# element.net
KiCad netlist of a schematic drawn in EAGLE
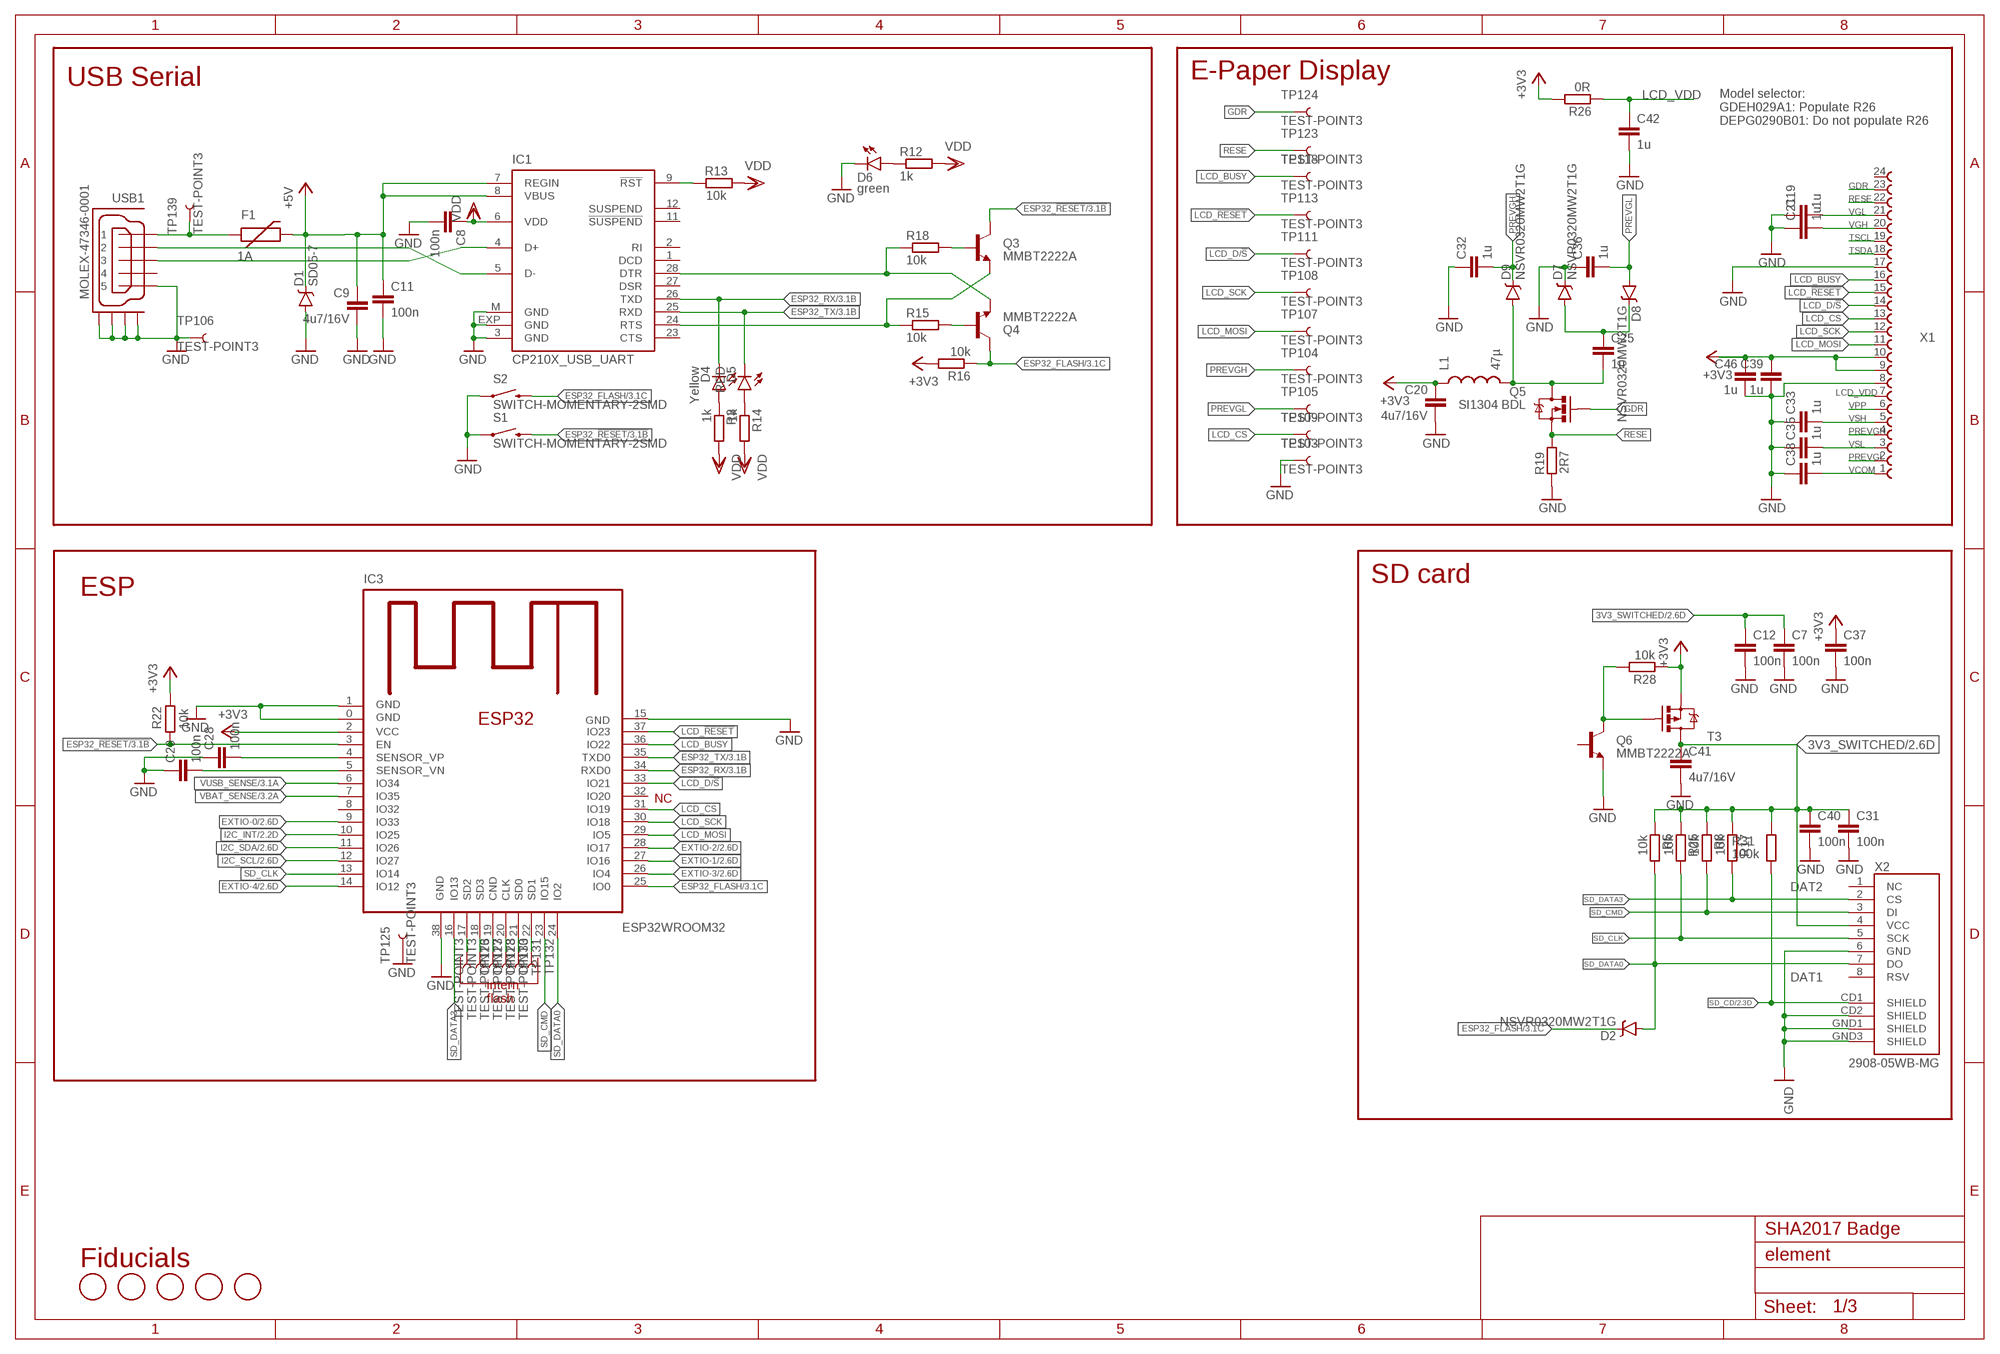
[diagram p0: schematic, sheet 1]
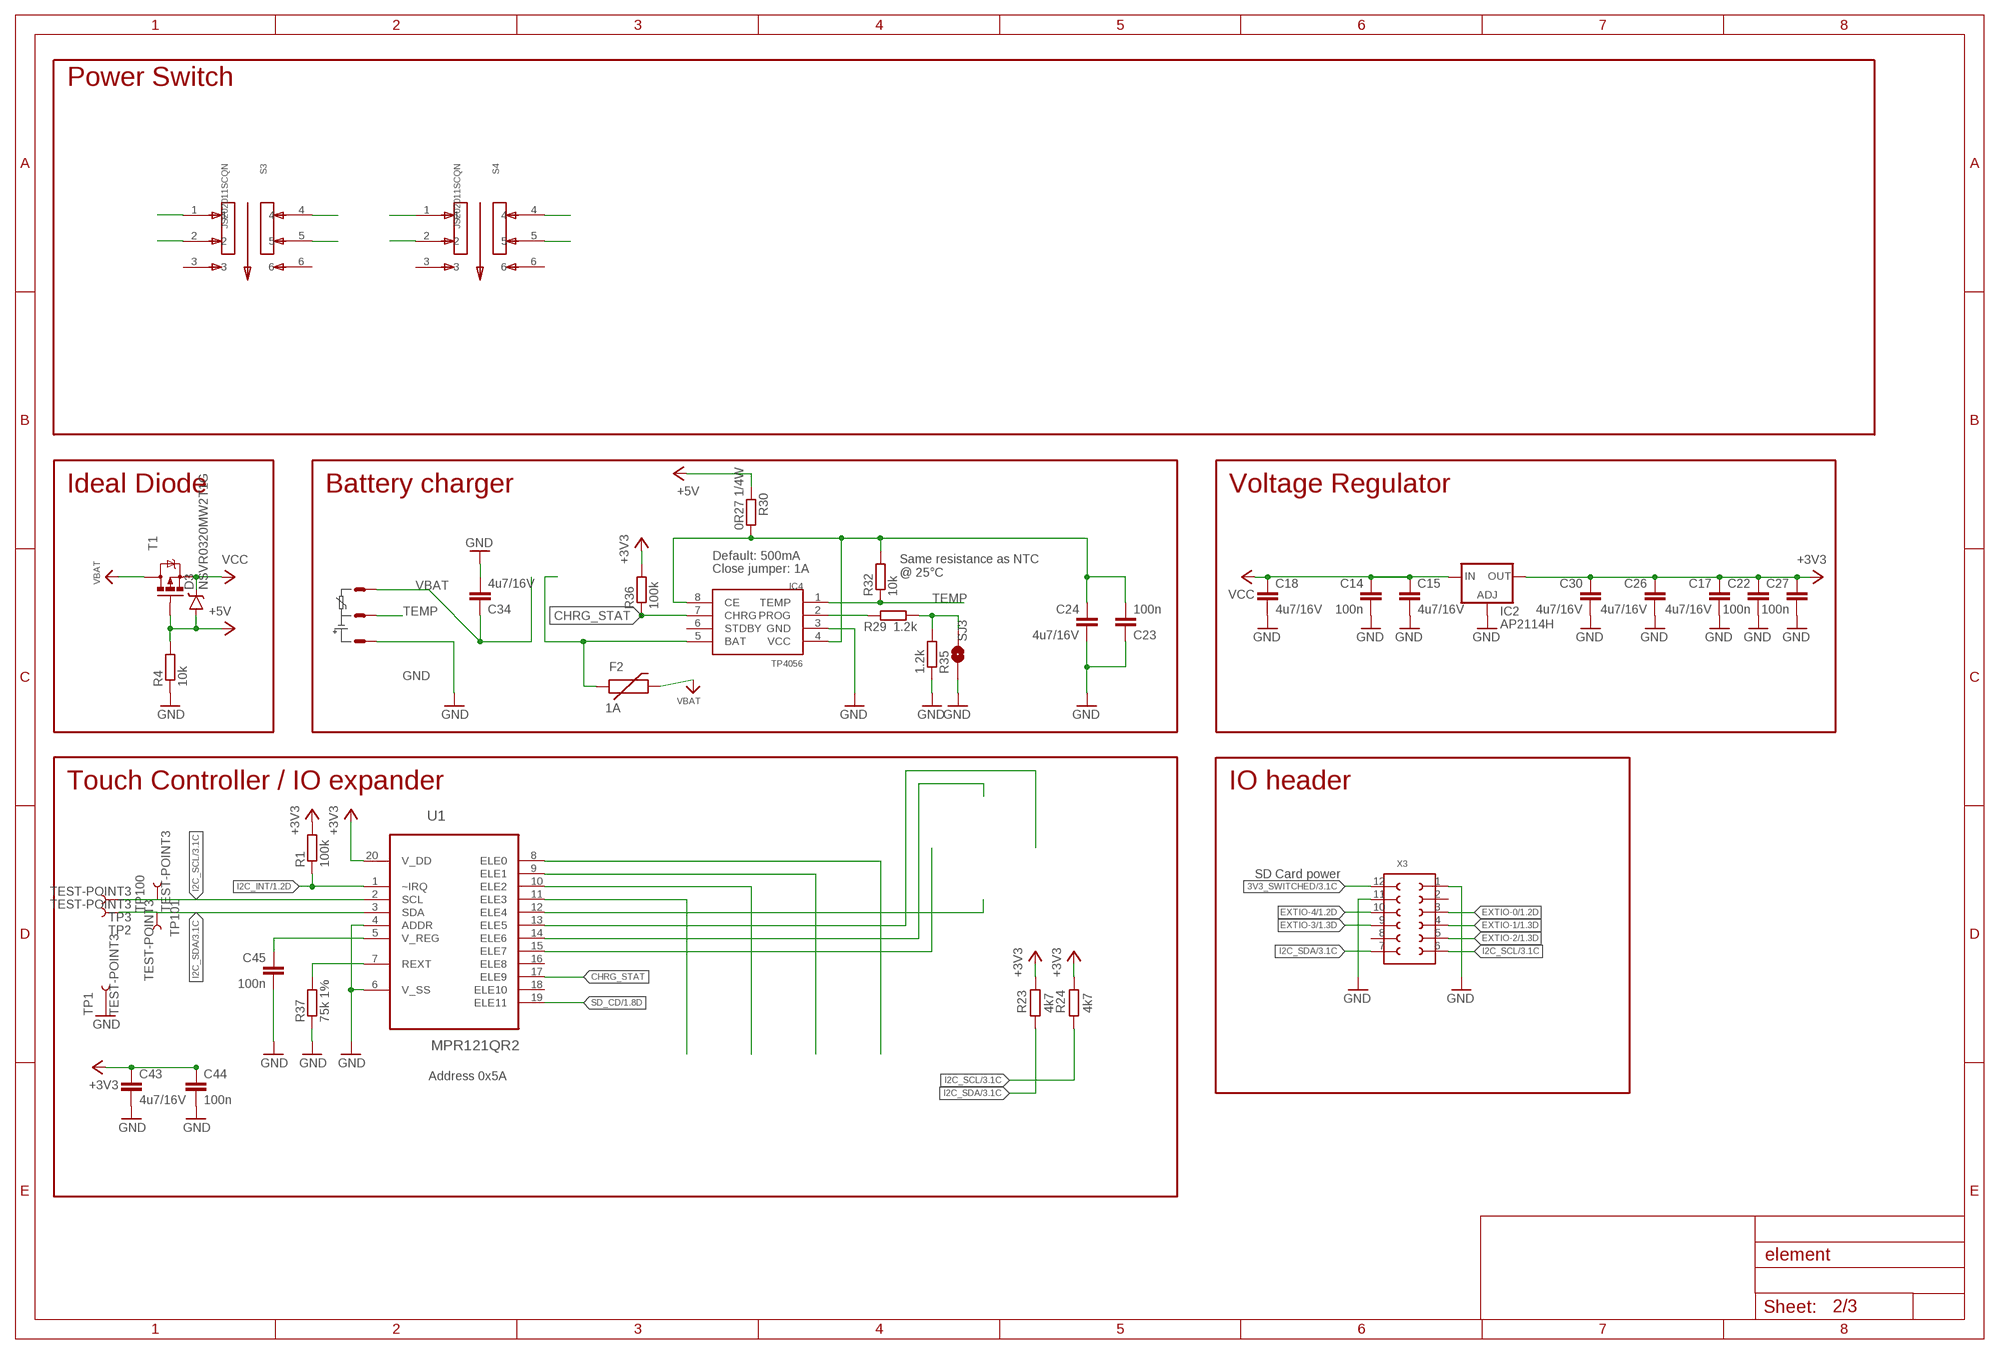
[diagram p1: schematic, sheet 2]
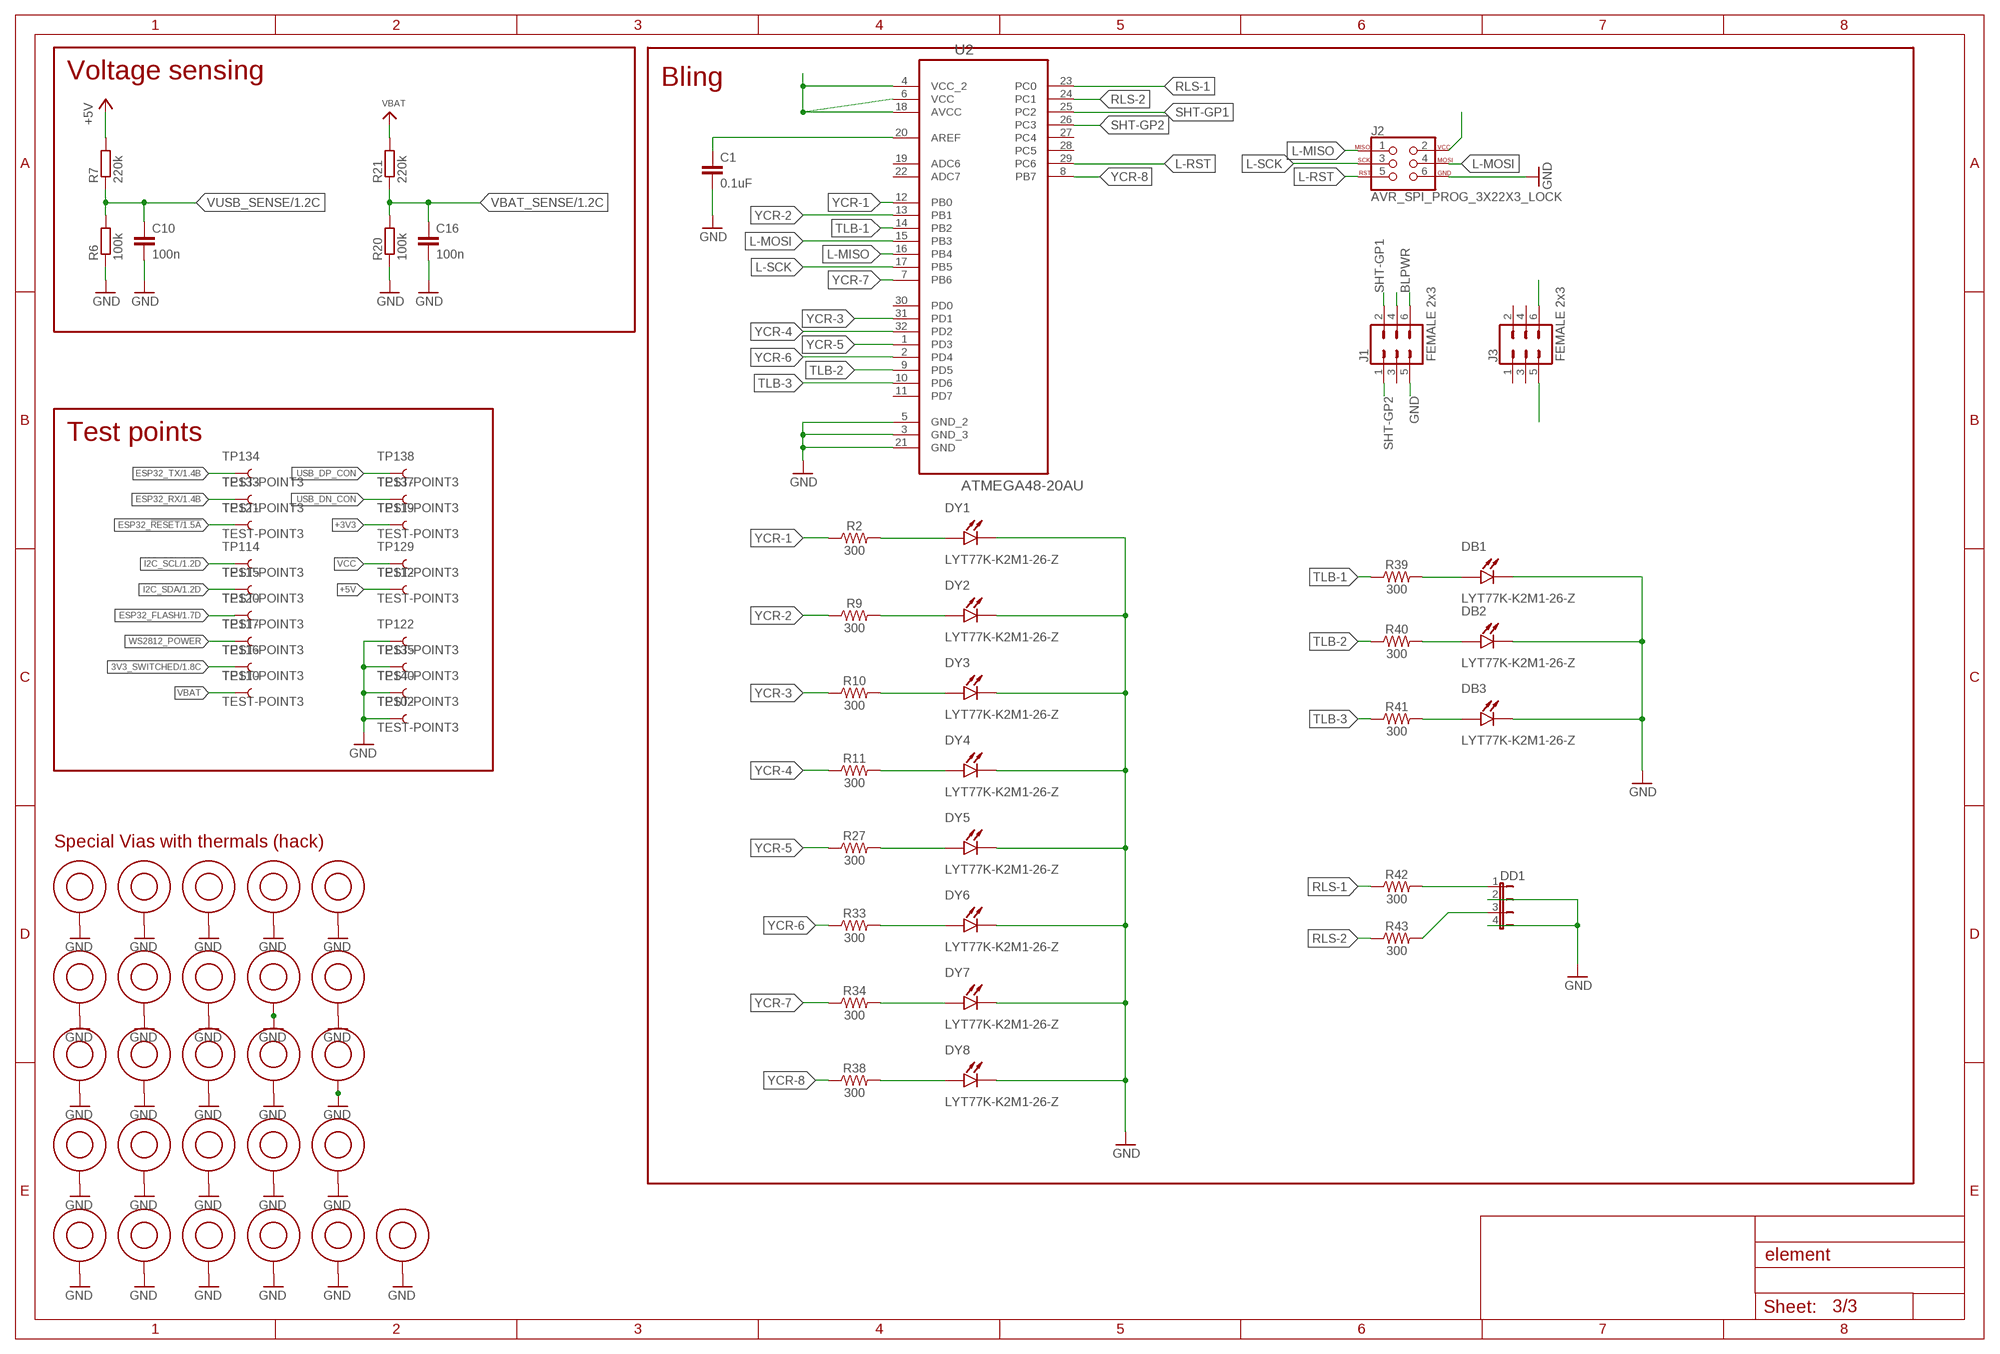
[diagram p2: schematic, sheet 3]

(export (version "E")
  (design (tool "Eeschema 10.0.6"))
  (components
    (comp (ref "$$U$1")
      (value "VIA")
      (footprint "eagle-import:VIA")
      (fields (field (name "PARTNO") "NAP"))
      (libsource (lib "eagle-import") (part "VIA"))
    )
    (comp (ref "$$U$2")
      (value "VIA")
      (footprint "eagle-import:VIA")
      (fields (field (name "PARTNO") "NAP"))
      (libsource (lib "eagle-import") (part "VIA"))
    )
    (comp (ref "$$U$3")
      (value "VIA")
      (footprint "eagle-import:VIA")
      (fields (field (name "PARTNO") "NAP"))
      (libsource (lib "eagle-import") (part "VIA"))
    )
    (comp (ref "$$U$4")
      (value "VIA")
      (footprint "eagle-import:VIA")
      (fields (field (name "PARTNO") "NAP"))
      (libsource (lib "eagle-import") (part "VIA"))
    )
    (comp (ref "$$U$5")
      (value "VIA")
      (footprint "eagle-import:VIA")
      (fields (field (name "PARTNO") "NAP"))
      (libsource (lib "eagle-import") (part "VIA"))
    )
    (comp (ref "$$U$6")
      (value "VIA")
      (footprint "eagle-import:VIA")
      (fields (field (name "PARTNO") "NAP"))
      (libsource (lib "eagle-import") (part "VIA"))
    )
    (comp (ref "$$U$7")
      (value "VIA")
      (footprint "eagle-import:VIA")
      (fields (field (name "PARTNO") "NAP"))
      (libsource (lib "eagle-import") (part "VIA"))
    )
    (comp (ref "$$U$8")
      (value "VIA")
      (footprint "eagle-import:VIA")
      (fields (field (name "PARTNO") "NAP"))
      (libsource (lib "eagle-import") (part "VIA"))
    )
    (comp (ref "$$U$9")
      (value "VIA")
      (footprint "eagle-import:VIA")
      (fields (field (name "PARTNO") "NAP"))
      (libsource (lib "eagle-import") (part "VIA"))
    )
    (comp (ref "C1")
      (value "0.1uF")
      (footprint "eagle-import:0603")
      (libsource (lib "eagle-import") (part "0.1UF-0603-25V-5%"))
    )
    (comp (ref "C10")
      (value "100n")
      (footprint "eagle-import:C0603-DASHES")
      (fields (field (name "PARTNO") "GRM188R71H104KA93D"))
      (libsource (lib "eagle-import") (part "C0603-DASHES"))
    )
    (comp (ref "C16")
      (value "100n")
      (footprint "eagle-import:C0603-DASHES")
      (fields (field (name "PARTNO") "GRM188R71H104KA93D"))
      (libsource (lib "eagle-import") (part "C0603-DASHES"))
    )
    (comp (ref "DB1")
      (value "LYT77K-K2M1-26-Z")
      (footprint "eagle-import:LED_LYT77K-K2M1-26-Z")
      (fields (field (name "MF") "Osram"))
      (libsource (lib "eagle-import") (part "LYT77K-K2M1-26-Z"))
    )
    (comp (ref "DB2")
      (value "LYT77K-K2M1-26-Z")
      (footprint "eagle-import:LED_LYT77K-K2M1-26-Z")
      (fields (field (name "MF") "Osram"))
      (libsource (lib "eagle-import") (part "LYT77K-K2M1-26-Z"))
    )
    (comp (ref "DB3")
      (value "LYT77K-K2M1-26-Z")
      (footprint "eagle-import:LED_LYT77K-K2M1-26-Z")
      (fields (field (name "MF") "Osram"))
      (libsource (lib "eagle-import") (part "LYT77K-K2M1-26-Z"))
    )
    (comp (ref "DD1")
      (value "JP4E")
      (footprint "eagle-import:JP4")
      (libsource (lib "eagle-import") (part "JP4E"))
    )
    (comp (ref "DY1")
      (value "LYT77K-K2M1-26-Z")
      (footprint "eagle-import:LED_LYT77K-K2M1-26-Z")
      (fields (field (name "MF") "Osram"))
      (libsource (lib "eagle-import") (part "LYT77K-K2M1-26-Z"))
    )
    (comp (ref "DY2")
      (value "LYT77K-K2M1-26-Z")
      (footprint "eagle-import:LED_LYT77K-K2M1-26-Z")
      (fields (field (name "MF") "Osram"))
      (libsource (lib "eagle-import") (part "LYT77K-K2M1-26-Z"))
    )
    (comp (ref "DY3")
      (value "LYT77K-K2M1-26-Z")
      (footprint "eagle-import:LED_LYT77K-K2M1-26-Z")
      (fields (field (name "MF") "Osram"))
      (libsource (lib "eagle-import") (part "LYT77K-K2M1-26-Z"))
    )
    (comp (ref "DY4")
      (value "LYT77K-K2M1-26-Z")
      (footprint "eagle-import:LED_LYT77K-K2M1-26-Z")
      (fields (field (name "MF") "Osram"))
      (libsource (lib "eagle-import") (part "LYT77K-K2M1-26-Z"))
    )
    (comp (ref "DY5")
      (value "LYT77K-K2M1-26-Z")
      (footprint "eagle-import:LED_LYT77K-K2M1-26-Z")
      (fields (field (name "MF") "Osram"))
      (libsource (lib "eagle-import") (part "LYT77K-K2M1-26-Z"))
    )
    (comp (ref "DY6")
      (value "LYT77K-K2M1-26-Z")
      (footprint "eagle-import:LED_LYT77K-K2M1-26-Z")
      (fields (field (name "MF") "Osram"))
      (libsource (lib "eagle-import") (part "LYT77K-K2M1-26-Z"))
    )
    (comp (ref "DY7")
      (value "LYT77K-K2M1-26-Z")
      (footprint "eagle-import:LED_LYT77K-K2M1-26-Z")
      (fields (field (name "MF") "Osram"))
      (libsource (lib "eagle-import") (part "LYT77K-K2M1-26-Z"))
    )
    (comp (ref "DY8")
      (value "LYT77K-K2M1-26-Z")
      (footprint "eagle-import:LED_LYT77K-K2M1-26-Z")
      (fields (field (name "MF") "Osram"))
      (libsource (lib "eagle-import") (part "LYT77K-K2M1-26-Z"))
    )
    (comp (ref "J1")
      (value "FEMALE 2x3")
      (footprint "eagle-import:2X3")
      (libsource (lib "eagle-import") (part "CONN_03X2FEMALE"))
    )
    (comp (ref "J2")
      (value "AVR_SPI_PROG_3X22X3_LOCK")
      (footprint "eagle-import:2X3_LOCK")
      (libsource (lib "eagle-import") (part "AVR_SPI_PROG_3X22X3_LOCK"))
    )
    (comp (ref "J3")
      (value "FEMALE 2x3")
      (footprint "eagle-import:2X3")
      (libsource (lib "eagle-import") (part "CONN_03X2FEMALE"))
    )
    (comp (ref "R2")
      (value "300")
      (footprint "eagle-import:0603")
      (libsource (lib "eagle-import") (part "300OHM-0603-1/10W-1%"))
    )
    (comp (ref "R6")
      (value "100k")
      (footprint "eagle-import:R0603-DASHES")
      (fields (field (name "PARTNO") "ERJ-3GEYJ104V"))
      (libsource (lib "eagle-import") (part "sha2017_rev0_1_0_dev_R0603-DASHES"))
    )
    (comp (ref "R7")
      (value "220k")
      (footprint "eagle-import:R0603-DASHES")
      (fields (field (name "PARTNO") "ERJ-3GEYJ224V"))
      (libsource (lib "eagle-import") (part "sha2017_rev0_1_0_dev_R0603-DASHES"))
    )
    (comp (ref "R9")
      (value "300")
      (footprint "eagle-import:0603")
      (libsource (lib "eagle-import") (part "300OHM-0603-1/10W-1%"))
    )
    (comp (ref "R10")
      (value "300")
      (footprint "eagle-import:0603")
      (libsource (lib "eagle-import") (part "300OHM-0603-1/10W-1%"))
    )
    (comp (ref "R11")
      (value "300")
      (footprint "eagle-import:0603")
      (libsource (lib "eagle-import") (part "300OHM-0603-1/10W-1%"))
    )
    (comp (ref "R20")
      (value "100k")
      (footprint "eagle-import:R0603-DASHES")
      (fields (field (name "PARTNO") "ERJ-3GEYJ104V"))
      (libsource (lib "eagle-import") (part "sha2017_rev0_1_0_dev_R0603-DASHES"))
    )
    (comp (ref "R21")
      (value "220k")
      (footprint "eagle-import:R0603-DASHES")
      (fields (field (name "PARTNO") "ERJ-3GEYJ224V"))
      (libsource (lib "eagle-import") (part "sha2017_rev0_1_0_dev_R0603-DASHES"))
    )
    (comp (ref "R27")
      (value "300")
      (footprint "eagle-import:0603")
      (libsource (lib "eagle-import") (part "300OHM-0603-1/10W-1%"))
    )
    (comp (ref "R33")
      (value "300")
      (footprint "eagle-import:0603")
      (libsource (lib "eagle-import") (part "300OHM-0603-1/10W-1%"))
    )
    (comp (ref "R34")
      (value "300")
      (footprint "eagle-import:0603")
      (libsource (lib "eagle-import") (part "300OHM-0603-1/10W-1%"))
    )
    (comp (ref "R38")
      (value "300")
      (footprint "eagle-import:0603")
      (libsource (lib "eagle-import") (part "300OHM-0603-1/10W-1%"))
    )
    (comp (ref "R39")
      (value "300")
      (footprint "eagle-import:0603")
      (libsource (lib "eagle-import") (part "300OHM-0603-1/10W-1%"))
    )
    (comp (ref "R40")
      (value "300")
      (footprint "eagle-import:0603")
      (libsource (lib "eagle-import") (part "300OHM-0603-1/10W-1%"))
    )
    (comp (ref "R41")
      (value "300")
      (footprint "eagle-import:0603")
      (libsource (lib "eagle-import") (part "300OHM-0603-1/10W-1%"))
    )
    (comp (ref "R42")
      (value "300")
      (footprint "eagle-import:0603")
      (libsource (lib "eagle-import") (part "300OHM-0603-1/10W-1%"))
    )
    (comp (ref "R43")
      (value "300")
      (footprint "eagle-import:0603")
      (libsource (lib "eagle-import") (part "300OHM-0603-1/10W-1%"))
    )
    (comp (ref "TP102")
      (value "TEST-POINT3")
      (footprint "eagle-import:PAD.03X.03")
      (fields (field (name "PARTNO") "NAP"))
      (libsource (lib "eagle-import") (part "TEST-POINT3"))
    )
    (comp (ref "TP110")
      (value "TEST-POINT3")
      (footprint "eagle-import:PAD.03X.03")
      (fields (field (name "PARTNO") "NAP"))
      (libsource (lib "eagle-import") (part "TEST-POINT3"))
    )
    (comp (ref "TP112")
      (value "TEST-POINT3")
      (footprint "eagle-import:PAD.03X.03")
      (fields (field (name "PARTNO") "NAP"))
      (libsource (lib "eagle-import") (part "TEST-POINT3"))
    )
    (comp (ref "TP114")
      (value "TEST-POINT3")
      (footprint "eagle-import:PAD.03X.03")
      (fields (field (name "PARTNO") "NAP"))
      (libsource (lib "eagle-import") (part "TEST-POINT3"))
    )
    (comp (ref "TP115")
      (value "TEST-POINT3")
      (footprint "eagle-import:PAD.03X.03")
      (fields (field (name "PARTNO") "NAP"))
      (libsource (lib "eagle-import") (part "TEST-POINT3"))
    )
    (comp (ref "TP116")
      (value "TEST-POINT3")
      (footprint "eagle-import:PAD.03X.03")
      (fields (field (name "PARTNO") "NAP"))
      (libsource (lib "eagle-import") (part "TEST-POINT3"))
    )
    (comp (ref "TP117")
      (value "TEST-POINT3")
      (footprint "eagle-import:PAD.03X.03")
      (fields (field (name "PARTNO") "NAP"))
      (libsource (lib "eagle-import") (part "TEST-POINT3"))
    )
    (comp (ref "TP119")
      (value "TEST-POINT3")
      (footprint "eagle-import:PAD.03X.03")
      (fields (field (name "PARTNO") "NAP"))
      (libsource (lib "eagle-import") (part "TEST-POINT3"))
    )
    (comp (ref "TP120")
      (value "TEST-POINT3")
      (footprint "eagle-import:PAD.03X.03")
      (fields (field (name "PARTNO") "NAP"))
      (libsource (lib "eagle-import") (part "TEST-POINT3"))
    )
    (comp (ref "TP121")
      (value "TEST-POINT3")
      (footprint "eagle-import:PAD.03X.03")
      (fields (field (name "PARTNO") "NAP"))
      (libsource (lib "eagle-import") (part "TEST-POINT3"))
    )
    (comp (ref "TP122")
      (value "TEST-POINT3")
      (footprint "eagle-import:PAD.03X.03")
      (fields (field (name "PARTNO") "NAP"))
      (libsource (lib "eagle-import") (part "TEST-POINT3"))
    )
    (comp (ref "TP129")
      (value "TEST-POINT3")
      (footprint "eagle-import:PAD.03X.03")
      (fields (field (name "PARTNO") "NAP"))
      (libsource (lib "eagle-import") (part "TEST-POINT3"))
    )
    (comp (ref "TP133")
      (value "TEST-POINT3")
      (footprint "eagle-import:PAD.03X.03")
      (fields (field (name "PARTNO") "NAP"))
      (libsource (lib "eagle-import") (part "TEST-POINT3"))
    )
    (comp (ref "TP134")
      (value "TEST-POINT3")
      (footprint "eagle-import:PAD.03X.03")
      (fields (field (name "PARTNO") "NAP"))
      (libsource (lib "eagle-import") (part "TEST-POINT3"))
    )
    (comp (ref "TP135")
      (value "TEST-POINT3")
      (footprint "eagle-import:PAD.03X.03")
      (fields (field (name "PARTNO") "NAP"))
      (libsource (lib "eagle-import") (part "TEST-POINT3"))
    )
    (comp (ref "TP137")
      (value "TEST-POINT3")
      (footprint "eagle-import:PAD.03X.03")
      (fields (field (name "PARTNO") "NAP"))
      (libsource (lib "eagle-import") (part "TEST-POINT3"))
    )
    (comp (ref "TP138")
      (value "TEST-POINT3")
      (footprint "eagle-import:PAD.03X.03")
      (fields (field (name "PARTNO") "NAP"))
      (libsource (lib "eagle-import") (part "TEST-POINT3"))
    )
    (comp (ref "TP140")
      (value "TEST-POINT3")
      (footprint "eagle-import:PAD.03X.03")
      (fields (field (name "PARTNO") "NAP"))
      (libsource (lib "eagle-import") (part "TEST-POINT3"))
    )
    (comp (ref "U$2")
      (value "VIA")
      (footprint "eagle-import:VIA")
      (fields (field (name "PARTNO") "NAP"))
      (libsource (lib "eagle-import") (part "VIA"))
    )
    (comp (ref "U$3")
      (value "VIA")
      (footprint "eagle-import:VIA")
      (fields (field (name "PARTNO") "NAP"))
      (libsource (lib "eagle-import") (part "VIA"))
    )
    (comp (ref "U$4")
      (value "VIA")
      (footprint "eagle-import:VIA")
      (fields (field (name "PARTNO") "NAP"))
      (libsource (lib "eagle-import") (part "VIA"))
    )
    (comp (ref "U$5")
      (value "VIA")
      (footprint "eagle-import:VIA")
      (fields (field (name "PARTNO") "NAP"))
      (libsource (lib "eagle-import") (part "VIA"))
    )
    (comp (ref "U$6")
      (value "VIA")
      (footprint "eagle-import:VIA")
      (fields (field (name "PARTNO") "NAP"))
      (libsource (lib "eagle-import") (part "VIA"))
    )
    (comp (ref "U$10")
      (value "VIA")
      (footprint "eagle-import:VIA")
      (fields (field (name "PARTNO") "NAP"))
      (libsource (lib "eagle-import") (part "VIA"))
    )
    (comp (ref "U$11")
      (value "VIA")
      (footprint "eagle-import:VIA")
      (fields (field (name "PARTNO") "NAP"))
      (libsource (lib "eagle-import") (part "VIA"))
    )
    (comp (ref "U$12")
      (value "VIA")
      (footprint "eagle-import:VIA")
      (fields (field (name "PARTNO") "NAP"))
      (libsource (lib "eagle-import") (part "VIA"))
    )
    (comp (ref "U$13")
      (value "VIA")
      (footprint "eagle-import:VIA")
      (fields (field (name "PARTNO") "NAP"))
      (libsource (lib "eagle-import") (part "VIA"))
    )
    (comp (ref "U$14")
      (value "VIA")
      (footprint "eagle-import:VIA")
      (fields (field (name "PARTNO") "NAP"))
      (libsource (lib "eagle-import") (part "VIA"))
    )
    (comp (ref "U$15")
      (value "VIA")
      (footprint "eagle-import:VIA")
      (fields (field (name "PARTNO") "NAP"))
      (libsource (lib "eagle-import") (part "VIA"))
    )
    (comp (ref "U$16")
      (value "VIA")
      (footprint "eagle-import:VIA")
      (fields (field (name "PARTNO") "NAP"))
      (libsource (lib "eagle-import") (part "VIA"))
    )
    (comp (ref "U$17")
      (value "VIA")
      (footprint "eagle-import:VIA")
      (fields (field (name "PARTNO") "NAP"))
      (libsource (lib "eagle-import") (part "VIA"))
    )
    (comp (ref "U$18")
      (value "VIA")
      (footprint "eagle-import:VIA")
      (fields (field (name "PARTNO") "NAP"))
      (libsource (lib "eagle-import") (part "VIA"))
    )
    (comp (ref "U$19")
      (value "VIA")
      (footprint "eagle-import:VIA")
      (fields (field (name "PARTNO") "NAP"))
      (libsource (lib "eagle-import") (part "VIA"))
    )
    (comp (ref "U$20")
      (value "VIA")
      (footprint "eagle-import:VIA")
      (fields (field (name "PARTNO") "NAP"))
      (libsource (lib "eagle-import") (part "VIA"))
    )
    (comp (ref "U$21")
      (value "VIA")
      (footprint "eagle-import:VIA")
      (fields (field (name "PARTNO") "NAP"))
      (libsource (lib "eagle-import") (part "VIA"))
    )
    (comp (ref "U$22")
      (value "VIA")
      (footprint "eagle-import:VIA")
      (fields (field (name "PARTNO") "NAP"))
      (libsource (lib "eagle-import") (part "VIA"))
    )
    (comp (ref "U$23")
      (value "VIA")
      (footprint "eagle-import:VIA")
      (fields (field (name "PARTNO") "NAP"))
      (libsource (lib "eagle-import") (part "VIA"))
    )
    (comp (ref "U2")
      (value "ATMEGA48-20AU")
      (footprint "eagle-import:QFP80P900X900X120-32N")
      (fields (field (name "MF") "Microchip"))
      (libsource (lib "eagle-import") (part "ATMEGA48-20AU"))
    )
    (comp (ref "C7")
      (value "100n")
      (footprint "eagle-import:C0603-DASHES")
      (fields (field (name "PARTNO") "GRM188R71H104KA93D"))
      (libsource (lib "eagle-import") (part "C0603-DASHES"))
    )
    (comp (ref "C8")
      (value "100n")
      (footprint "eagle-import:C0603-DASHES")
      (fields (field (name "PARTNO") "GRM188R71H104KA93D"))
      (libsource (lib "eagle-import") (part "C0603-DASHES"))
    )
    (comp (ref "C9")
      (value "4u7/16V")
      (footprint "eagle-import:C0805")
      (fields (field (name "PARTNO") "GRM21BR61C475KA88K"))
      (libsource (lib "eagle-import") (part "C-EUC0805"))
    )
    (comp (ref "C11")
      (value "100n")
      (footprint "eagle-import:C0603-DASHES")
      (fields (field (name "PARTNO") "GRM188R71H104KA93D"))
      (libsource (lib "eagle-import") (part "C0603-DASHES"))
    )
    (comp (ref "C12")
      (value "100n")
      (footprint "eagle-import:C0603-DASHES")
      (fields (field (name "PARTNO") "GRM188R71H104KA93D"))
      (libsource (lib "eagle-import") (part "C0603-DASHES"))
    )
    (comp (ref "C19")
      (value "1u")
      (footprint "eagle-import:C0603-DASHES")
      (fields (field (name "PARTNO") "GRM188R61E105KA12D"))
      (libsource (lib "eagle-import") (part "C0603-DASHES"))
    )
    (comp (ref "C20")
      (value "4u7/16V")
      (footprint "eagle-import:C0805")
      (fields (field (name "PARTNO") "GRM21BR61C475KA88K"))
      (libsource (lib "eagle-import") (part "C-EUC0805"))
    )
    (comp (ref "C21")
      (value "1u")
      (footprint "eagle-import:C0603-DASHES")
      (fields (field (name "PARTNO") "GRM188R61E105KA12D"))
      (libsource (lib "eagle-import") (part "C0603-DASHES"))
    )
    (comp (ref "C25")
      (value "1u")
      (footprint "eagle-import:C0603-DASHES")
      (fields (field (name "PARTNO") "GRM188R61E105KA12D"))
      (libsource (lib "eagle-import") (part "C0603-DASHES"))
    )
    (comp (ref "C28")
      (value "100n")
      (footprint "eagle-import:C0603-DASHES")
      (fields (field (name "PARTNO") "GRM188R71H104KA93D"))
      (libsource (lib "eagle-import") (part "C0603-DASHES"))
    )
    (comp (ref "C29")
      (value "100n")
      (footprint "eagle-import:C0603-DASHES")
      (fields (field (name "PARTNO") "GRM188R71H104KA93D"))
      (libsource (lib "eagle-import") (part "C0603-DASHES"))
    )
    (comp (ref "C31")
      (value "100n")
      (footprint "eagle-import:C0603-DASHES")
      (fields (field (name "PARTNO") "GRM188R71H104KA93D"))
      (libsource (lib "eagle-import") (part "C0603-DASHES"))
    )
    (comp (ref "C32")
      (value "1u")
      (footprint "eagle-import:C0603-DASHES")
      (fields (field (name "PARTNO") "GRM188R61E105KA12D"))
      (libsource (lib "eagle-import") (part "C0603-DASHES"))
    )
    (comp (ref "C33")
      (value "1u")
      (footprint "eagle-import:C0603-DASHES")
      (fields (field (name "PARTNO") "GRM188R61E105KA12D"))
      (libsource (lib "eagle-import") (part "C0603-DASHES"))
    )
    (comp (ref "C35")
      (value "1u")
      (footprint "eagle-import:C0603-DASHES")
      (fields (field (name "PARTNO") "GRM188R61E105KA12D"))
      (libsource (lib "eagle-import") (part "C0603-DASHES"))
    )
    (comp (ref "C36")
      (value "1u")
      (footprint "eagle-import:C0603-DASHES")
      (fields (field (name "PARTNO") "GRM188R61E105KA12D"))
      (libsource (lib "eagle-import") (part "C0603-DASHES"))
    )
    (comp (ref "C37")
      (value "100n")
      (footprint "eagle-import:C0603-DASHES")
      (fields (field (name "PARTNO") "GRM188R71H104KA93D"))
      (libsource (lib "eagle-import") (part "C0603-DASHES"))
    )
    (comp (ref "C38")
      (value "1u")
      (footprint "eagle-import:C0603-DASHES")
      (fields (field (name "PARTNO") "GRM188R61E105KA12D"))
      (libsource (lib "eagle-import") (part "C0603-DASHES"))
    )
    (comp (ref "C39")
      (value "1u")
      (footprint "eagle-import:C0603-DASHES")
      (fields (field (name "PARTNO") "GRM188R61E105KA12D"))
      (libsource (lib "eagle-import") (part "C0603-DASHES"))
    )
    (comp (ref "C40")
      (value "100n")
      (footprint "eagle-import:C0603-DASHES")
      (fields (field (name "PARTNO") "GRM188R71H104KA93D"))
      (libsource (lib "eagle-import") (part "C0603-DASHES"))
    )
    (comp (ref "C41")
      (value "4u7/16V")
      (footprint "eagle-import:C0805")
      (fields (field (name "PARTNO") "GRM21BR61C475KA88K"))
      (libsource (lib "eagle-import") (part "C-EUC0805"))
    )
    (comp (ref "C42")
      (value "1u")
      (footprint "eagle-import:C0603-DASHES")
      (fields (field (name "PARTNO") "GRM188R61E105KA12D"))
      (libsource (lib "eagle-import") (part "C0603-DASHES"))
    )
    (comp (ref "C46")
      (value "1u")
      (footprint "eagle-import:C0603-DASHES")
      (fields (field (name "PARTNO") "GRM188R61E105KA12D"))
      (libsource (lib "eagle-import") (part "C0603-DASHES"))
    )
    (comp (ref "D1")
      (value "SD05-7")
      (footprint "eagle-import:SOD-323")
      (libsource (lib "eagle-import") (part "DIODE-SCHOTTKY-PMEG4005EJ"))
    )
    (comp (ref "D2")
      (value "NSVR0320MW2T1G")
      (footprint "eagle-import:SOD-323")
      (fields (field (name "PARTNO") "BAT20JFILM"))
      (libsource (lib "eagle-import") (part "BAT20JFILM"))
    )
    (comp (ref "D4")
      (value "Yellow")
      (footprint "eagle-import:LED-0603")
      (libsource (lib "eagle-import") (part "LED0603"))
    )
    (comp (ref "D5")
      (value "RED")
      (footprint "eagle-import:LED-0603")
      (libsource (lib "eagle-import") (part "LED0603"))
    )
    (comp (ref "D6")
      (value "green")
      (footprint "eagle-import:LED-0603")
      (libsource (lib "eagle-import") (part "LED0603"))
    )
    (comp (ref "D7")
      (value "NSVR0320MW2T1G")
      (footprint "eagle-import:SOD-323")
      (fields (field (name "PARTNO") "BAT20JFILM"))
      (libsource (lib "eagle-import") (part "BAT20JFILM"))
    )
    (comp (ref "D8")
      (value "NSVR0320MW2T1G")
      (footprint "eagle-import:SOD-323")
      (fields (field (name "PARTNO") "BAT20JFILM"))
      (libsource (lib "eagle-import") (part "BAT20JFILM"))
    )
    (comp (ref "D9")
      (value "NSVR0320MW2T1G")
      (footprint "eagle-import:SOD-323")
      (fields (field (name "PARTNO") "BAT20JFILM"))
      (libsource (lib "eagle-import") (part "BAT20JFILM"))
    )
    (comp (ref "F1")
      (value "1A")
      (footprint "eagle-import:PTC-1206")
      (libsource (lib "eagle-import") (part "PTCSMD"))
    )
    (comp (ref "FD1")
      (value "FIDUCIAL")
      (footprint "eagle-import:FIDUCIAL_1MM")
      (fields (field (name "PARTNO") "NAP"))
      (libsource (lib "eagle-import") (part "FIDUCIAL"))
    )
    (comp (ref "FD2")
      (value "FIDUCIAL")
      (footprint "eagle-import:FIDUCIAL_1MM")
      (fields (field (name "PARTNO") "NAP"))
      (libsource (lib "eagle-import") (part "FIDUCIAL"))
    )
    (comp (ref "FD3")
      (value "FIDUCIAL")
      (footprint "eagle-import:FIDUCIAL_1MM")
      (fields (field (name "PARTNO") "NAP"))
      (libsource (lib "eagle-import") (part "FIDUCIAL"))
    )
    (comp (ref "FD4")
      (value "FIDUCIAL")
      (footprint "eagle-import:FIDUCIAL_1MM")
      (fields (field (name "PARTNO") "NAP"))
      (libsource (lib "eagle-import") (part "FIDUCIAL"))
    )
    (comp (ref "FD5")
      (value "FIDUCIAL")
      (footprint "eagle-import:FIDUCIAL_1MM")
      (fields (field (name "PARTNO") "NAP"))
      (libsource (lib "eagle-import") (part "FIDUCIAL"))
    )
    (comp (ref "IC1")
      (value "CP210X_USB_UART")
      (footprint "eagle-import:MLP28")
      (fields (field (name "PARTNO") "CP2102-GMR"))
      (libsource (lib "eagle-import") (part "CP210X_USB_UART"))
    )
    (comp (ref "IC3")
      (value "ESP32WROOM32")
      (footprint "eagle-import:ESP32MOD")
      (libsource (lib "eagle-import") (part "ESP32WROOM32"))
    )
    (comp (ref "L1")
      (value "47µ")
      (footprint "eagle-import:1210")
      (fields (field (name "PARTNO") "NLCV32T-220K-EF"))
      (libsource (lib "eagle-import") (part "INDUCTOR1210"))
    )
    (comp (ref "Q3")
      (value "MMBT2222A")
      (footprint "eagle-import:SOT23-3")
      (fields (field (name "PARTNO") "BC817-25,215"))
      (libsource (lib "eagle-import") (part "TRANSISTOR_NPNMMBT2222A"))
    )
    (comp (ref "Q4")
      (value "MMBT2222A")
      (footprint "eagle-import:SOT23-3")
      (fields (field (name "PARTNO") "BC817-25,215"))
      (libsource (lib "eagle-import") (part "TRANSISTOR_NPNMMBT2222A"))
    )
    (comp (ref "Q5")
      (value "SI1304 BDL")
      (footprint "eagle-import:SOT323")
      (fields (field (name "PARTNO") "SI1308EDL-T1-GE3"))
      (libsource (lib "eagle-import") (part "MOSFET-NCHANNEL2N7002PW"))
    )
    (comp (ref "Q6")
      (value "MMBT2222A")
      (footprint "eagle-import:SOT23-3")
      (fields (field (name "PARTNO") "BC817-25,215"))
      (libsource (lib "eagle-import") (part "TRANSISTOR_NPNMMBT2222A"))
    )
    (comp (ref "R3")
      (value "1k")
      (footprint "eagle-import:R0603-DASHES")
      (fields (field (name "PARTNO") "ERJ-3GEYJ102V"))
      (libsource (lib "eagle-import") (part "sha2017_rev0_1_0_dev_R0603-DASHES"))
    )
    (comp (ref "R5")
      (value "10k")
      (footprint "eagle-import:R0603-DASHES")
      (fields (field (name "PARTNO") "ERJ-3GEYJ103V"))
      (libsource (lib "eagle-import") (part "R0603-DASHES"))
    )
    (comp (ref "R8")
      (value "10k")
      (footprint "eagle-import:R0603-DASHES")
      (fields (field (name "PARTNO") "ERJ-3GEYJ103V"))
      (libsource (lib "eagle-import") (part "R0603-DASHES"))
    )
    (comp (ref "R12")
      (value "1k")
      (footprint "eagle-import:R0603-DASHES")
      (fields (field (name "PARTNO") "ERJ-3GEYJ102V"))
      (libsource (lib "eagle-import") (part "sha2017_rev0_1_0_dev_R0603-DASHES"))
    )
    (comp (ref "R13")
      (value "10k")
      (footprint "eagle-import:R0603-DASHES")
      (fields (field (name "PARTNO") "ERJ-3GEYJ103V"))
      (libsource (lib "eagle-import") (part "sha2017_rev0_1_0_dev_R0603-DASHES"))
    )
    (comp (ref "R14")
      (value "1k")
      (footprint "eagle-import:R0603-DASHES")
      (fields (field (name "PARTNO") "ERJ-3GEYJ102V"))
      (libsource (lib "eagle-import") (part "sha2017_rev0_1_0_dev_R0603-DASHES"))
    )
    (comp (ref "R15")
      (value "10k")
      (footprint "eagle-import:R0603-DASHES")
      (fields (field (name "PARTNO") "ERJ-3GEYJ103V"))
      (libsource (lib "eagle-import") (part "sha2017_rev0_1_0_dev_R0603-DASHES"))
    )
    (comp (ref "R16")
      (value "10k")
      (footprint "eagle-import:R0603-DASHES")
      (fields (field (name "PARTNO") "ERJ-3GEYJ103V"))
      (libsource (lib "eagle-import") (part "sha2017_rev0_1_0_dev_R0603-DASHES"))
    )
    (comp (ref "R17")
      (value "10k")
      (footprint "eagle-import:R0603-DASHES")
      (fields (field (name "PARTNO") "ERJ-3GEYJ103V"))
      (libsource (lib "eagle-import") (part "sha2017_rev0_1_0_dev_R0603-DASHES"))
    )
    (comp (ref "R18")
      (value "10k")
      (footprint "eagle-import:R0603-DASHES")
      (fields (field (name "PARTNO") "ERJ-3GEYJ103V"))
      (libsource (lib "eagle-import") (part "sha2017_rev0_1_0_dev_R0603-DASHES"))
    )
    (comp (ref "R19")
      (value "2R7")
      (footprint "eagle-import:R0603-DASHES")
      (fields (field (name "PARTNO") "ERJ-3GEYJ5R1V"))
      (libsource (lib "eagle-import") (part "sha2017_rev0_1_0_dev_R0603-DASHES"))
    )
    (comp (ref "R22")
      (value "10k")
      (footprint "eagle-import:R0603-DASHES")
      (fields (field (name "PARTNO") "ERJ-3GEYJ103V"))
      (libsource (lib "eagle-import") (part "sha2017_rev0_1_0_dev_R0603-DASHES"))
    )
    (comp (ref "R25")
      (value "10k")
      (footprint "eagle-import:R0603-DASHES")
      (fields (field (name "PARTNO") "ERJ-3GEYJ103V"))
      (libsource (lib "eagle-import") (part "sha2017_rev0_1_0_dev_R0603-DASHES"))
    )
    (comp (ref "R26")
      (value "0R")
      (footprint "eagle-import:R0603-DASHES")
      (fields (field (name "PARTNO") "ERJ-3GEYJ5R1V"))
      (libsource (lib "eagle-import") (part "sha2017_rev0_1_0_dev_R0603-DASHES"))
    )
    (comp (ref "R28")
      (value "10k")
      (footprint "eagle-import:R0603-DASHES")
      (fields (field (name "PARTNO") "ERJ-3GEYJ103V"))
      (libsource (lib "eagle-import") (part "R0603-DASHES"))
    )
    (comp (ref "R31")
      (value "100k")
      (footprint "eagle-import:R0603-DASHES")
      (fields (field (name "PARTNO") "ERJ-3GEYJ104V"))
      (libsource (lib "eagle-import") (part "sha2017_rev0_1_0_dev_R0603-DASHES"))
    )
    (comp (ref "S1")
      (value "SWITCH-MOMENTARY-2SMD")
      (footprint "eagle-import:TACTILE-SWITCH-SMD")
      (fields (field (name "PARTNO") "SKQGABE010"))
      (libsource (lib "eagle-import") (part "SWITCH-MOMENTARY-2SMD"))
    )
    (comp (ref "S2")
      (value "SWITCH-MOMENTARY-2SMD")
      (footprint "eagle-import:TACTILE-SWITCH-SMD")
      (fields (field (name "PARTNO") "SKQGABE010"))
      (libsource (lib "eagle-import") (part "SWITCH-MOMENTARY-2SMD"))
    )
    (comp (ref "T3")
      (value "MOSFET-PCHANNEL")
      (footprint "eagle-import:SOT23-3")
      (libsource (lib "eagle-import") (part "MOSFET-PCHANNEL"))
    )
    (comp (ref "TP103")
      (value "TEST-POINT3")
      (footprint "eagle-import:PAD.03X.03")
      (fields (field (name "PARTNO") "NAP"))
      (libsource (lib "eagle-import") (part "TEST-POINT3"))
    )
    (comp (ref "TP104")
      (value "TEST-POINT3")
      (footprint "eagle-import:PAD.03X.03")
      (fields (field (name "PARTNO") "NAP"))
      (libsource (lib "eagle-import") (part "TEST-POINT3"))
    )
    (comp (ref "TP105")
      (value "TEST-POINT3")
      (footprint "eagle-import:PAD.03X.03")
      (fields (field (name "PARTNO") "NAP"))
      (libsource (lib "eagle-import") (part "TEST-POINT3"))
    )
    (comp (ref "TP106")
      (value "TEST-POINT3")
      (footprint "eagle-import:PAD.03X.03")
      (fields (field (name "PARTNO") "NAP"))
      (libsource (lib "eagle-import") (part "TEST-POINT3"))
    )
    (comp (ref "TP107")
      (value "TEST-POINT3")
      (footprint "eagle-import:PAD.03X.03")
      (fields (field (name "PARTNO") "NAP"))
      (libsource (lib "eagle-import") (part "TEST-POINT3"))
    )
    (comp (ref "TP108")
      (value "TEST-POINT3")
      (footprint "eagle-import:PAD.03X.03")
      (fields (field (name "PARTNO") "NAP"))
      (libsource (lib "eagle-import") (part "TEST-POINT3"))
    )
    (comp (ref "TP109")
      (value "TEST-POINT3")
      (footprint "eagle-import:PAD.03X.03")
      (fields (field (name "PARTNO") "NAP"))
      (libsource (lib "eagle-import") (part "TEST-POINT3"))
    )
    (comp (ref "TP111")
      (value "TEST-POINT3")
      (footprint "eagle-import:PAD.03X.03")
      (fields (field (name "PARTNO") "NAP"))
      (libsource (lib "eagle-import") (part "TEST-POINT3"))
    )
    (comp (ref "TP113")
      (value "TEST-POINT3")
      (footprint "eagle-import:PAD.03X.03")
      (fields (field (name "PARTNO") "NAP"))
      (libsource (lib "eagle-import") (part "TEST-POINT3"))
    )
    (comp (ref "TP118")
      (value "TEST-POINT3")
      (footprint "eagle-import:PAD.03X.03")
      (fields (field (name "PARTNO") "NAP"))
      (libsource (lib "eagle-import") (part "TEST-POINT3"))
    )
    (comp (ref "TP123")
      (value "TEST-POINT3")
      (footprint "eagle-import:PAD.03X.03")
      (fields (field (name "PARTNO") "NAP"))
      (libsource (lib "eagle-import") (part "TEST-POINT3"))
    )
    (comp (ref "TP124")
      (value "TEST-POINT3")
      (footprint "eagle-import:PAD.03X.03")
      (fields (field (name "PARTNO") "NAP"))
      (libsource (lib "eagle-import") (part "TEST-POINT3"))
    )
    (comp (ref "TP125")
      (value "TEST-POINT3")
      (footprint "eagle-import:PAD.03X.03")
      (fields (field (name "PARTNO") "NAP"))
      (libsource (lib "eagle-import") (part "TEST-POINT3"))
    )
    (comp (ref "TP126")
      (value "TEST-POINT3")
      (footprint "eagle-import:PAD.03X.03")
      (fields (field (name "PARTNO") "NAP"))
      (libsource (lib "eagle-import") (part "TEST-POINT3"))
    )
    (comp (ref "TP127")
      (value "TEST-POINT3")
      (footprint "eagle-import:PAD.03X.03")
      (fields (field (name "PARTNO") "NAP"))
      (libsource (lib "eagle-import") (part "TEST-POINT3"))
    )
    (comp (ref "TP128")
      (value "TEST-POINT3")
      (footprint "eagle-import:PAD.03X.03")
      (fields (field (name "PARTNO") "NAP"))
      (libsource (lib "eagle-import") (part "TEST-POINT3"))
    )
    (comp (ref "TP130")
      (value "TEST-POINT3")
      (footprint "eagle-import:PAD.03X.03")
      (fields (field (name "PARTNO") "NAP"))
      (libsource (lib "eagle-import") (part "TEST-POINT3"))
    )
    (comp (ref "TP131")
      (value "TEST-POINT3")
      (footprint "eagle-import:PAD.03X.03")
      (fields (field (name "PARTNO") "NAP"))
      (libsource (lib "eagle-import") (part "TEST-POINT3"))
    )
    (comp (ref "TP132")
      (value "TEST-POINT3")
      (footprint "eagle-import:PAD.03X.03")
      (fields (field (name "PARTNO") "NAP"))
      (libsource (lib "eagle-import") (part "TEST-POINT3"))
    )
    (comp (ref "TP139")
      (value "TEST-POINT3")
      (footprint "eagle-import:PAD.03X.03")
      (fields (field (name "PARTNO") "NAP"))
      (libsource (lib "eagle-import") (part "TEST-POINT3"))
    )
    (comp (ref "USB1")
      (value "MOLEX-47346-0001")
      (footprint "eagle-import:MOLEX-47364-0001")
      (fields (field (name "PARTNO") "10118192-0001LF"))
      (libsource (lib "eagle-import") (part "MOLEX-47346-0001"))
    )
    (comp (ref "X1")
      (value "68712414022")
      (footprint "eagle-import:68712414022")
      (libsource (lib "eagle-import") (part "68712414022"))
    )
    (comp (ref "X2")
      (value "2908-05WB-MG")
      (footprint "eagle-import:MICRO-SD-SOCKET-PP")
      (libsource (lib "eagle-import") (part "2908-05WB-MG"))
    )
    (comp (ref "C14")
      (value "100n")
      (footprint "eagle-import:C0603-DASHES")
      (fields (field (name "PARTNO") "GRM188R71H104KA93D"))
      (libsource (lib "eagle-import") (part "C0603-DASHES"))
    )
    (comp (ref "C15")
      (value "4u7/16V")
      (footprint "eagle-import:C0805")
      (fields (field (name "PARTNO") "GRM21BR61C475KA88K"))
      (libsource (lib "eagle-import") (part "C-EUC0805"))
    )
    (comp (ref "C17")
      (value "4u7/16V")
      (footprint "eagle-import:C0805")
      (fields (field (name "PARTNO") "GRM21BR61C475KA88K"))
      (libsource (lib "eagle-import") (part "C-EUC0805"))
    )
    (comp (ref "C18")
      (value "4u7/16V")
      (footprint "eagle-import:C0805")
      (fields (field (name "PARTNO") "GRM21BR61C475KA88K"))
      (libsource (lib "eagle-import") (part "C-EUC0805"))
    )
    (comp (ref "C22")
      (value "100n")
      (footprint "eagle-import:C0603-DASHES")
      (fields (field (name "PARTNO") "GRM188R71H104KA93D"))
      (libsource (lib "eagle-import") (part "C0603-DASHES"))
    )
    (comp (ref "C23")
      (value "100n")
      (footprint "eagle-import:C0603-DASHES")
      (fields (field (name "PARTNO") "GRM188R71H104KA93D"))
      (libsource (lib "eagle-import") (part "C0603-DASHES"))
    )
    (comp (ref "C24")
      (value "4u7/16V")
      (footprint "eagle-import:C0805")
      (fields (field (name "PARTNO") "GRM21BR61C475KA88K"))
      (libsource (lib "eagle-import") (part "C-EUC0805"))
    )
    (comp (ref "C26")
      (value "4u7/16V")
      (footprint "eagle-import:C0805")
      (fields (field (name "PARTNO") "GRM21BR61C475KA88K"))
      (libsource (lib "eagle-import") (part "C-EUC0805"))
    )
    (comp (ref "C27")
      (value "100n")
      (footprint "eagle-import:C0603-DASHES")
      (fields (field (name "PARTNO") "GRM188R71H104KA93D"))
      (libsource (lib "eagle-import") (part "C0603-DASHES"))
    )
    (comp (ref "C30")
      (value "4u7/16V")
      (footprint "eagle-import:C0805")
      (fields (field (name "PARTNO") "GRM21BR61C475KA88K"))
      (libsource (lib "eagle-import") (part "C-EUC0805"))
    )
    (comp (ref "C34")
      (value "4u7/16V")
      (footprint "eagle-import:C0805")
      (fields (field (name "PARTNO") "GRM21BR61C475KA88K"))
      (libsource (lib "eagle-import") (part "C-EUC0805"))
    )
    (comp (ref "C43")
      (value "4u7/16V")
      (footprint "eagle-import:C0805")
      (fields (field (name "PARTNO") "GRM21BR61C475KA88K"))
      (libsource (lib "eagle-import") (part "C-EUC0805"))
    )
    (comp (ref "C44")
      (value "100n")
      (footprint "eagle-import:C0603-DASHES")
      (fields (field (name "PARTNO") "GRM188R71H104KA93D"))
      (libsource (lib "eagle-import") (part "C0603-DASHES"))
    )
    (comp (ref "C45")
      (value "100n")
      (footprint "eagle-import:C0603-DASHES")
      (fields (field (name "PARTNO") "GRM188R71H104KA93D"))
      (libsource (lib "eagle-import") (part "C0603-DASHES"))
    )
    (comp (ref "D3")
      (value "NSVR0320MW2T1G")
      (footprint "eagle-import:SOD-323")
      (fields (field (name "PARTNO") "BAT20JFILM"))
      (libsource (lib "eagle-import") (part "BAT20JFILM"))
    )
    (comp (ref "F2")
      (value "1A")
      (footprint "eagle-import:PTC-1206")
      (libsource (lib "eagle-import") (part "PTCSMD"))
    )
    (comp (ref "IC2")
      (value "AP2114H")
      (footprint "eagle-import:SOT223")
      (fields (field (name "PARTNO") "AP7215-33YG-13"))
      (libsource (lib "eagle-import") (part "LD117A?S33TR"))
    )
    (comp (ref "IC4")
      (value "TP4056")
      (footprint "eagle-import:SOP-8")
      (libsource (lib "eagle-import") (part "TP4056"))
    )
    (comp (ref "R1")
      (value "100k")
      (footprint "eagle-import:R0603-DASHES")
      (fields (field (name "PARTNO") "ERJ-3GEYJ104V"))
      (libsource (lib "eagle-import") (part "sha2017_rev0_1_0_dev_R0603-DASHES"))
    )
    (comp (ref "R4")
      (value "10k")
      (footprint "eagle-import:R0603-DASHES")
      (fields (field (name "PARTNO") "ERJ-3GEYJ103V"))
      (libsource (lib "eagle-import") (part "sha2017_rev0_1_0_dev_R0603-DASHES"))
    )
    (comp (ref "R23")
      (value "4k7")
      (footprint "eagle-import:R0603-DASHES")
      (fields (field (name "PARTNO") "ERJ-3GEYJ103V"))
      (libsource (lib "eagle-import") (part "sha2017_rev0_1_0_dev_R0603-DASHES"))
    )
    (comp (ref "R24")
      (value "4k7")
      (footprint "eagle-import:R0603-DASHES")
      (fields (field (name "PARTNO") "ERJ-3GEYJ103V"))
      (libsource (lib "eagle-import") (part "sha2017_rev0_1_0_dev_R0603-DASHES"))
    )
    (comp (ref "R29")
      (value "1.2k")
      (footprint "eagle-import:R0603-DASHES")
      (fields (field (name "PARTNO") "ERJ-3GEYJ222V"))
      (libsource (lib "eagle-import") (part "sha2017_rev0_1_0_dev_R0603-DASHES"))
    )
    (comp (ref "R30")
      (value "0R27 1/4W")
      (footprint "eagle-import:R1206")
      (fields (field (name "PARTNO") "ERJ-3GEYJ154V"))
      (libsource (lib "eagle-import") (part "R-EU_R1206"))
    )
    (comp (ref "R32")
      (value "10k")
      (footprint "eagle-import:R0603-DASHES")
      (fields (field (name "PARTNO") "ERJ-3GEYJ154V"))
      (libsource (lib "eagle-import") (part "sha2017_rev0_1_0_dev_R0603-DASHES"))
    )
    (comp (ref "R35")
      (value "1.2k")
      (footprint "eagle-import:R0603-DASHES")
      (fields (field (name "PARTNO") "ERJ-3GEYJ222V"))
      (libsource (lib "eagle-import") (part "sha2017_rev0_1_0_dev_R0603-DASHES"))
    )
    (comp (ref "R36")
      (value "100k")
      (footprint "eagle-import:R0603-DASHES")
      (fields (field (name "PARTNO") "ERJ-3GEYJ104V"))
      (libsource (lib "eagle-import") (part "sha2017_rev0_1_0_dev_R0603-DASHES"))
    )
    (comp (ref "R37")
      (value "75k 1%")
      (footprint "eagle-import:R0603-DASHES")
      (fields (field (name "PARTNO") "ERJ-3GEYJ104V"))
      (libsource (lib "eagle-import") (part "sha2017_rev0_1_0_dev_R0603-DASHES"))
    )
    (comp (ref "S3")
      (value "JS202011SCQN")
      (footprint "eagle-import:SW_JS202011SCQN")
      (fields (field (name "MF") "C&K"))
      (libsource (lib "eagle-import") (part "JS202011SCQN"))
    )
    (comp (ref "S4")
      (value "JS202011SCQN")
      (footprint "eagle-import:SW_JS202011SCQN")
      (fields (field (name "MF") "C&K"))
      (libsource (lib "eagle-import") (part "JS202011SCQN"))
    )
    (comp (ref "SJ3")
      (value "JUMPER-PAD-2-NOYES_SILK")
      (footprint "eagle-import:PAD-JUMPER-2-NO_YES_SILK")
      (fields (field (name "PARTNO") "NAP"))
      (libsource (lib "eagle-import") (part "JUMPER-PAD-2-NOYES_SILK"))
    )
    (comp (ref "T1")
      (value "MOSFET-PCHANNEL")
      (footprint "eagle-import:SOT23-3")
      (libsource (lib "eagle-import") (part "MOSFET-PCHANNEL"))
    )
    (comp (ref "TP1")
      (value "TEST-POINT3")
      (footprint "eagle-import:PAD.03X.03")
      (fields (field (name "PARTNO") "NAP"))
      (libsource (lib "eagle-import") (part "TEST-POINT3"))
    )
    (comp (ref "TP2")
      (value "TEST-POINT3")
      (footprint "eagle-import:PAD.03X.03")
      (fields (field (name "PARTNO") "NAP"))
      (libsource (lib "eagle-import") (part "TEST-POINT3"))
    )
    (comp (ref "TP3")
      (value "TEST-POINT3")
      (footprint "eagle-import:PAD.03X.03")
      (fields (field (name "PARTNO") "NAP"))
      (libsource (lib "eagle-import") (part "TEST-POINT3"))
    )
    (comp (ref "TP100")
      (value "TEST-POINT3")
      (footprint "eagle-import:PAD.03X.03")
      (fields (field (name "PARTNO") "NAP"))
      (libsource (lib "eagle-import") (part "TEST-POINT3"))
    )
    (comp (ref "TP101")
      (value "TEST-POINT3")
      (footprint "eagle-import:PAD.03X.03")
      (fields (field (name "PARTNO") "NAP"))
      (libsource (lib "eagle-import") (part "TEST-POINT3"))
    )
    (comp (ref "U1")
      (value "MPR121QR2")
      (footprint "eagle-import:QFN40P300X300X60-20N")
      (libsource (lib "eagle-import") (part "MPR121QR2"))
    )
    (comp (ref "X3")
      (value "610X12243021")
      (footprint "eagle-import:610X12243021")
      (fields (field (name "PARTNO") "517-153208-2020-TB"))
      (libsource (lib "eagle-import") (part "610X12243021"))
    )
    (comp (ref "X4")
      (value "JST-PH3")
      (footprint "eagle-import:JST-PH3")
      (libsource (lib "eagle-import") (part "JST-PH3"))
    )
  )
  (nets
    (net (code "1") (name "+3V3") (class "Default")
      (node (ref "C17") (pin "1") (pinfunction "1_1") (pintype "passive"))
      (node (ref "C20") (pin "1") (pinfunction "1_1") (pintype "passive"))
      (node (ref "C22") (pin "1") (pinfunction "1_1") (pintype "passive"))
      (node (ref "C26") (pin "1") (pinfunction "1_1") (pintype "passive"))
      (node (ref "C27") (pin "1") (pinfunction "1_1") (pintype "passive"))
      (node (ref "C30") (pin "1") (pinfunction "1_1") (pintype "passive"))
      (node (ref "C37") (pin "1") (pinfunction "1_1") (pintype "passive"))
      (node (ref "C39") (pin "1") (pinfunction "1_1") (pintype "passive"))
      (node (ref "C43") (pin "1") (pinfunction "1_1") (pintype "passive"))
      (node (ref "C44") (pin "1") (pinfunction "1_1") (pintype "passive"))
      (node (ref "C46") (pin "1") (pinfunction "1_1") (pintype "passive"))
      (node (ref "IC2") (pin "4") (pinfunction "OUT_4") (pintype "passive"))
      (node (ref "IC3") (pin "2") (pinfunction "VCC_2") (pintype "power_in"))
      (node (ref "L1") (pin "1") (pinfunction "1_1") (pintype "passive"))
      (node (ref "R1") (pin "2") (pinfunction "2_2") (pintype "passive"))
      (node (ref "R16") (pin "2") (pinfunction "2_2") (pintype "passive"))
      (node (ref "R22") (pin "1") (pinfunction "1_1") (pintype "passive"))
      (node (ref "R23") (pin "1") (pinfunction "1_1") (pintype "passive"))
      (node (ref "R24") (pin "1") (pinfunction "1_1") (pintype "passive"))
      (node (ref "R26") (pin "1") (pinfunction "1_1") (pintype "passive"))
      (node (ref "R28") (pin "2") (pinfunction "2_2") (pintype "passive"))
      (node (ref "R36") (pin "2") (pinfunction "2_2") (pintype "passive"))
      (node (ref "T3") (pin "2") (pinfunction "S_2") (pintype "passive"))
      (node (ref "TP119") (pin "P$1") (pinfunction "1_P$1") (pintype "bidirectional"))
      (node (ref "U1") (pin "20") (pinfunction "V_DD_20") (pintype "power_in"))
      (node (ref "X1") (pin "10") (pinfunction "10_10") (pintype "passive"))
      (node (ref "X1") (pin "9") (pinfunction "9_9") (pintype "passive"))
    )
    (net (code "2") (name "+5V") (class "Default")
      (node (ref "C11") (pin "1") (pinfunction "1_1") (pintype "passive"))
      (node (ref "C9") (pin "1") (pinfunction "1_1") (pintype "passive"))
      (node (ref "D1") (pin "C") (pinfunction "C_C") (pintype "passive"))
      (node (ref "D3") (pin "A") (pinfunction "A_A") (pintype "passive"))
      (node (ref "F1") (pin "2") (pinfunction "2_2") (pintype "bidirectional"))
      (node (ref "IC1") (pin "7") (pinfunction "REGIN_7") (pintype "passive"))
      (node (ref "IC1") (pin "8") (pinfunction "VBUS_8") (pintype "input"))
      (node (ref "R30") (pin "1") (pinfunction "1_1") (pintype "passive"))
      (node (ref "R4") (pin "2") (pinfunction "2_2") (pintype "passive"))
      (node (ref "R7") (pin "2") (pinfunction "2_2") (pintype "passive"))
      (node (ref "T1") (pin "1") (pinfunction "G_1") (pintype "passive"))
      (node (ref "TP112") (pin "P$1") (pinfunction "1_P$1") (pintype "bidirectional"))
    )
    (net (code "3") (name "3V3_SWITCHED") (class "Default")
      (node (ref "C12") (pin "1") (pinfunction "1_1") (pintype "passive"))
      (node (ref "C31") (pin "1") (pinfunction "1_1") (pintype "passive"))
      (node (ref "C40") (pin "1") (pinfunction "1_1") (pintype "passive"))
      (node (ref "C41") (pin "1") (pinfunction "1_1") (pintype "passive"))
      (node (ref "C7") (pin "1") (pinfunction "1_1") (pintype "passive"))
      (node (ref "R17") (pin "2") (pinfunction "2_2") (pintype "passive"))
      (node (ref "R25") (pin "2") (pinfunction "2_2") (pintype "passive"))
      (node (ref "R31") (pin "1") (pinfunction "1_1") (pintype "passive"))
      (node (ref "R5") (pin "2") (pinfunction "2_2") (pintype "passive"))
      (node (ref "R8") (pin "2") (pinfunction "2_2") (pintype "passive"))
      (node (ref "T3") (pin "3") (pinfunction "D_3") (pintype "passive"))
      (node (ref "TP116") (pin "P$1") (pinfunction "1_P$1") (pintype "bidirectional"))
      (node (ref "X2") (pin "4") (pinfunction "VCC_4") (pintype "bidirectional"))
      (node (ref "X3") (pin "12") (pinfunction "1_12") (pintype "passive"))
    )
    (net (code "4") (name "BLPWR") (class "Default")
      (node (ref "J1") (pin "6") (pinfunction "6_6") (pintype "bidirectional"))
      (node (ref "J2") (pin "2") (pinfunction "2_2") (pintype "passive"))
      (node (ref "J3") (pin "6") (pinfunction "6_6") (pintype "bidirectional"))
      (node (ref "S4") (pin "1") (pinfunction "1_1") (pintype "passive"))
      (node (ref "S4") (pin "4") (pinfunction "4_4") (pintype "passive"))
      (node (ref "U2") (pin "18") (pinfunction "AVCC_18") (pintype "power_in"))
      (node (ref "U2") (pin "4") (pinfunction "VCC_2_4") (pintype "power_in"))
      (node (ref "U2") (pin "6") (pinfunction "VCC_6") (pintype "power_in"))
    )
    (net (code "5") (name "CHRG_STAT") (class "Default")
      (node (ref "IC4") (pin "7") (pinfunction "CHRG_7") (pintype "bidirectional"))
      (node (ref "R36") (pin "1") (pinfunction "1_1") (pintype "passive"))
      (node (ref "U1") (pin "17") (pinfunction "ELE9_17") (pintype "output"))
    )
    (net (code "6") (name "ESP32_FLASH") (class "Default")
      (node (ref "D2") (pin "C") (pinfunction "C_C") (pintype "passive"))
      (node (ref "IC3") (pin "25") (pinfunction "IO0_25") (pintype "bidirectional"))
      (node (ref "Q4") (pin "3") (pinfunction "C_3") (pintype "passive"))
      (node (ref "R16") (pin "1") (pinfunction "1_1") (pintype "passive"))
      (node (ref "S2") (pin "3") (pinfunction "2_3") (pintype "passive"))
      (node (ref "TP120") (pin "P$1") (pinfunction "1_P$1") (pintype "bidirectional"))
    )
    (net (code "7") (name "ESP32_RX") (class "Default")
      (node (ref "D4") (pin "C") (pinfunction "C_C") (pintype "passive"))
      (node (ref "IC1") (pin "26") (pinfunction "TXD_26") (pintype "output"))
      (node (ref "IC3") (pin "34") (pinfunction "RXD0_34") (pintype "bidirectional"))
      (node (ref "TP133") (pin "P$1") (pinfunction "1_P$1") (pintype "bidirectional"))
    )
    (net (code "8") (name "ESP32_TX") (class "Default")
      (node (ref "D5") (pin "C") (pinfunction "C_C") (pintype "passive"))
      (node (ref "IC1") (pin "25") (pinfunction "RXD_25") (pintype "input"))
      (node (ref "IC3") (pin "35") (pinfunction "TXD0_35") (pintype "bidirectional"))
      (node (ref "TP134") (pin "P$1") (pinfunction "1_P$1") (pintype "bidirectional"))
    )
    (net (code "9") (name "ESP32_~{RESET}") (class "Default")
      (node (ref "IC3") (pin "3") (pinfunction "EN_3") (pintype "bidirectional"))
      (node (ref "Q3") (pin "3") (pinfunction "C_3") (pintype "passive"))
      (node (ref "R22") (pin "2") (pinfunction "2_2") (pintype "passive"))
      (node (ref "S1") (pin "3") (pinfunction "2_3") (pintype "passive"))
      (node (ref "TP121") (pin "P$1") (pinfunction "1_P$1") (pintype "bidirectional"))
    )
    (net (code "10") (name "EXTIO-0") (class "Default")
      (node (ref "IC3") (pin "9") (pinfunction "IO33_9") (pintype "bidirectional"))
      (node (ref "X3") (pin "3") (pinfunction "10_3") (pintype "passive"))
    )
    (net (code "11") (name "EXTIO-1") (class "Default")
      (node (ref "IC3") (pin "27") (pinfunction "IO16_27") (pintype "bidirectional"))
      (node (ref "X3") (pin "4") (pinfunction "9_4") (pintype "passive"))
    )
    (net (code "12") (name "EXTIO-2") (class "Default")
      (node (ref "IC3") (pin "28") (pinfunction "IO17_28") (pintype "bidirectional"))
      (node (ref "X3") (pin "5") (pinfunction "8_5") (pintype "passive"))
    )
    (net (code "13") (name "EXTIO-3") (class "Default")
      (node (ref "IC3") (pin "26") (pinfunction "IO4_26") (pintype "bidirectional"))
      (node (ref "X3") (pin "9") (pinfunction "4_9") (pintype "passive"))
    )
    (net (code "14") (name "EXTIO-4") (class "Default")
      (node (ref "IC3") (pin "14") (pinfunction "IO12_14") (pintype "bidirectional"))
      (node (ref "X3") (pin "10") (pinfunction "3_10") (pintype "passive"))
    )
    (net (code "15") (name "GDR") (class "Default")
      (node (ref "Q5") (pin "1") (pinfunction "G_1") (pintype "passive"))
      (node (ref "TP124") (pin "P$1") (pinfunction "1_P$1") (pintype "bidirectional"))
      (node (ref "X1") (pin "23") (pinfunction "23_23") (pintype "passive"))
    )
    (net (code "16") (name "GND") (class "Default")
      (node (ref "$$U$1") (pin "P$1") (pinfunction "P$1_P$1") (pintype "bidirectional"))
      (node (ref "$$U$2") (pin "P$1") (pinfunction "P$1_P$1") (pintype "bidirectional"))
      (node (ref "$$U$3") (pin "P$1") (pinfunction "P$1_P$1") (pintype "bidirectional"))
      (node (ref "$$U$4") (pin "P$1") (pinfunction "P$1_P$1") (pintype "bidirectional"))
      (node (ref "$$U$5") (pin "P$1") (pinfunction "P$1_P$1") (pintype "bidirectional"))
      (node (ref "$$U$6") (pin "P$1") (pinfunction "P$1_P$1") (pintype "bidirectional"))
      (node (ref "$$U$7") (pin "P$1") (pinfunction "P$1_P$1") (pintype "bidirectional"))
      (node (ref "$$U$8") (pin "P$1") (pinfunction "P$1_P$1") (pintype "bidirectional"))
      (node (ref "$$U$9") (pin "P$1") (pinfunction "P$1_P$1") (pintype "bidirectional"))
      (node (ref "C1") (pin "2") (pinfunction "2_2") (pintype "passive"))
      (node (ref "C10") (pin "2") (pinfunction "2_2") (pintype "passive"))
      (node (ref "C11") (pin "2") (pinfunction "2_2") (pintype "passive"))
      (node (ref "C12") (pin "2") (pinfunction "2_2") (pintype "passive"))
      (node (ref "C14") (pin "2") (pinfunction "2_2") (pintype "passive"))
      (node (ref "C15") (pin "2") (pinfunction "2_2") (pintype "passive"))
      (node (ref "C16") (pin "2") (pinfunction "2_2") (pintype "passive"))
      (node (ref "C17") (pin "2") (pinfunction "2_2") (pintype "passive"))
      (node (ref "C18") (pin "2") (pinfunction "2_2") (pintype "passive"))
      (node (ref "C19") (pin "1") (pinfunction "1_1") (pintype "passive"))
      (node (ref "C20") (pin "2") (pinfunction "2_2") (pintype "passive"))
      (node (ref "C21") (pin "1") (pinfunction "1_1") (pintype "passive"))
      (node (ref "C22") (pin "2") (pinfunction "2_2") (pintype "passive"))
      (node (ref "C23") (pin "1") (pinfunction "1_1") (pintype "passive"))
      (node (ref "C24") (pin "2") (pinfunction "2_2") (pintype "passive"))
      (node (ref "C26") (pin "2") (pinfunction "2_2") (pintype "passive"))
      (node (ref "C27") (pin "2") (pinfunction "2_2") (pintype "passive"))
      (node (ref "C28") (pin "1") (pinfunction "1_1") (pintype "passive"))
      (node (ref "C29") (pin "1") (pinfunction "1_1") (pintype "passive"))
      (node (ref "C30") (pin "2") (pinfunction "2_2") (pintype "passive"))
      (node (ref "C31") (pin "2") (pinfunction "2_2") (pintype "passive"))
      (node (ref "C32") (pin "1") (pinfunction "1_1") (pintype "passive"))
      (node (ref "C33") (pin "1") (pinfunction "1_1") (pintype "passive"))
      (node (ref "C34") (pin "2") (pinfunction "2_2") (pintype "passive"))
      (node (ref "C35") (pin "1") (pinfunction "1_1") (pintype "passive"))
      (node (ref "C36") (pin "1") (pinfunction "1_1") (pintype "passive"))
      (node (ref "C37") (pin "2") (pinfunction "2_2") (pintype "passive"))
      (node (ref "C38") (pin "1") (pinfunction "1_1") (pintype "passive"))
      (node (ref "C39") (pin "2") (pinfunction "2_2") (pintype "passive"))
      (node (ref "C40") (pin "2") (pinfunction "2_2") (pintype "passive"))
      (node (ref "C41") (pin "2") (pinfunction "2_2") (pintype "passive"))
      (node (ref "C42") (pin "2") (pinfunction "2_2") (pintype "passive"))
      (node (ref "C43") (pin "2") (pinfunction "2_2") (pintype "passive"))
      (node (ref "C44") (pin "2") (pinfunction "2_2") (pintype "passive"))
      (node (ref "C45") (pin "2") (pinfunction "2_2") (pintype "passive"))
      (node (ref "C46") (pin "2") (pinfunction "2_2") (pintype "passive"))
      (node (ref "C7") (pin "2") (pinfunction "2_2") (pintype "passive"))
      (node (ref "C8") (pin "2") (pinfunction "2_2") (pintype "passive"))
      (node (ref "C9") (pin "2") (pinfunction "2_2") (pintype "passive"))
      (node (ref "D1") (pin "A") (pinfunction "A_A") (pintype "passive"))
      (node (ref "D6") (pin "C") (pinfunction "C_C") (pintype "passive"))
      (node (ref "D7") (pin "C") (pinfunction "C_C") (pintype "passive"))
      (node (ref "DB1") (pin "1") (pinfunction "C_1") (pintype "passive"))
      (node (ref "DB2") (pin "1") (pinfunction "C_1") (pintype "passive"))
      (node (ref "DB3") (pin "1") (pinfunction "C_1") (pintype "passive"))
      (node (ref "DD1") (pin "2") (pinfunction "2_2") (pintype "passive"))
      (node (ref "DD1") (pin "4") (pinfunction "4_4") (pintype "passive"))
      (node (ref "DY1") (pin "1") (pinfunction "C_1") (pintype "passive"))
      (node (ref "DY2") (pin "1") (pinfunction "C_1") (pintype "passive"))
      (node (ref "DY3") (pin "1") (pinfunction "C_1") (pintype "passive"))
      (node (ref "DY4") (pin "1") (pinfunction "C_1") (pintype "passive"))
      (node (ref "DY5") (pin "1") (pinfunction "C_1") (pintype "passive"))
      (node (ref "DY6") (pin "1") (pinfunction "C_1") (pintype "passive"))
      (node (ref "DY7") (pin "1") (pinfunction "C_1") (pintype "passive"))
      (node (ref "DY8") (pin "1") (pinfunction "C_1") (pintype "passive"))
      (node (ref "IC1") (pin "3") (pinfunction "GND_3") (pintype "power_in"))
      (node (ref "IC1") (pin "EXP") (pinfunction "GND_EXP") (pintype "power_in"))
      (node (ref "IC1") (pin "M") (pinfunction "GND_M") (pintype "power_in"))
      (node (ref "IC2") (pin "1") (pinfunction "ADJ_1") (pintype "input"))
      (node (ref "IC3") (pin "0") (pinfunction "GND_0") (pintype "power_in"))
      (node (ref "IC3") (pin "1") (pinfunction "GND_1") (pintype "power_in"))
      (node (ref "IC3") (pin "15") (pinfunction "GND_15") (pintype "power_in"))
      (node (ref "IC3") (pin "38") (pinfunction "GND_38") (pintype "power_in"))
      (node (ref "IC4") (pin "3") (pinfunction "GND_3") (pintype "bidirectional"))
      (node (ref "J1") (pin "5") (pinfunction "5_5") (pintype "bidirectional"))
      (node (ref "J2") (pin "6") (pinfunction "6_6") (pintype "passive"))
      (node (ref "J3") (pin "5") (pinfunction "5_5") (pintype "bidirectional"))
      (node (ref "Q6") (pin "2") (pinfunction "E_2") (pintype "passive"))
      (node (ref "R19") (pin "2") (pinfunction "2_2") (pintype "passive"))
      (node (ref "R20") (pin "1") (pinfunction "1_1") (pintype "passive"))
      (node (ref "R35") (pin "2") (pinfunction "2_2") (pintype "passive"))
      (node (ref "R37") (pin "1") (pinfunction "1_1") (pintype "passive"))
      (node (ref "R4") (pin "1") (pinfunction "1_1") (pintype "passive"))
      (node (ref "R6") (pin "1") (pinfunction "1_1") (pintype "passive"))
      (node (ref "S1") (pin "1") (pinfunction "1_1") (pintype "passive"))
      (node (ref "S2") (pin "1") (pinfunction "1_1") (pintype "passive"))
      (node (ref "SJ3") (pin "1") (pinfunction "1_1") (pintype "passive"))
      (node (ref "TP1") (pin "P$1") (pinfunction "1_P$1") (pintype "bidirectional"))
      (node (ref "TP102") (pin "P$1") (pinfunction "1_P$1") (pintype "bidirectional"))
      (node (ref "TP103") (pin "P$1") (pinfunction "1_P$1") (pintype "bidirectional"))
      (node (ref "TP106") (pin "P$1") (pinfunction "1_P$1") (pintype "bidirectional"))
      (node (ref "TP122") (pin "P$1") (pinfunction "1_P$1") (pintype "bidirectional"))
      (node (ref "TP125") (pin "P$1") (pinfunction "1_P$1") (pintype "bidirectional"))
      (node (ref "TP135") (pin "P$1") (pinfunction "1_P$1") (pintype "bidirectional"))
      (node (ref "TP140") (pin "P$1") (pinfunction "1_P$1") (pintype "bidirectional"))
      (node (ref "U$10") (pin "P$1") (pinfunction "P$1_P$1") (pintype "bidirectional"))
      (node (ref "U$11") (pin "P$1") (pinfunction "P$1_P$1") (pintype "bidirectional"))
      (node (ref "U$12") (pin "P$1") (pinfunction "P$1_P$1") (pintype "bidirectional"))
      (node (ref "U$13") (pin "P$1") (pinfunction "P$1_P$1") (pintype "bidirectional"))
      (node (ref "U$14") (pin "P$1") (pinfunction "P$1_P$1") (pintype "bidirectional"))
      (node (ref "U$15") (pin "P$1") (pinfunction "P$1_P$1") (pintype "bidirectional"))
      (node (ref "U$16") (pin "P$1") (pinfunction "P$1_P$1") (pintype "bidirectional"))
      (node (ref "U$17") (pin "P$1") (pinfunction "P$1_P$1") (pintype "bidirectional"))
      (node (ref "U$18") (pin "P$1") (pinfunction "P$1_P$1") (pintype "bidirectional"))
      (node (ref "U$19") (pin "P$1") (pinfunction "P$1_P$1") (pintype "bidirectional"))
      (node (ref "U$2") (pin "P$1") (pinfunction "P$1_P$1") (pintype "bidirectional"))
      (node (ref "U$20") (pin "P$1") (pinfunction "P$1_P$1") (pintype "bidirectional"))
      (node (ref "U$21") (pin "P$1") (pinfunction "P$1_P$1") (pintype "bidirectional"))
      (node (ref "U$22") (pin "P$1") (pinfunction "P$1_P$1") (pintype "bidirectional"))
      (node (ref "U$23") (pin "P$1") (pinfunction "P$1_P$1") (pintype "bidirectional"))
      (node (ref "U$3") (pin "P$1") (pinfunction "P$1_P$1") (pintype "bidirectional"))
      (node (ref "U$4") (pin "P$1") (pinfunction "P$1_P$1") (pintype "bidirectional"))
      (node (ref "U$5") (pin "P$1") (pinfunction "P$1_P$1") (pintype "bidirectional"))
      (node (ref "U$6") (pin "P$1") (pinfunction "P$1_P$1") (pintype "bidirectional"))
      (node (ref "U1") (pin "4") (pinfunction "ADDR_4") (pintype "input"))
      (node (ref "U1") (pin "6") (pinfunction "V_SS_6") (pintype "power_in"))
      (node (ref "U2") (pin "21") (pinfunction "GND_21") (pintype "passive"))
      (node (ref "U2") (pin "3") (pinfunction "GND_3_3") (pintype "passive"))
      (node (ref "U2") (pin "5") (pinfunction "GND_2_5") (pintype "passive"))
      (node (ref "USB1") (pin "5") (pinfunction "5_5") (pintype "input"))
      (node (ref "USB1") (pin "GND1") (pinfunction "GND1_GND1") (pintype "bidirectional"))
      (node (ref "USB1") (pin "GND2") (pinfunction "GND2_GND2") (pintype "bidirectional"))
      (node (ref "USB1") (pin "GND3") (pinfunction "GND3_GND3") (pintype "bidirectional"))
      (node (ref "USB1") (pin "GND4") (pinfunction "GND4_GND4") (pintype "bidirectional"))
      (node (ref "X1") (pin "17") (pinfunction "17_17") (pintype "passive"))
      (node (ref "X1") (pin "8") (pinfunction "8_8") (pintype "passive"))
      (node (ref "X2") (pin "6") (pinfunction "GND_6") (pintype "bidirectional"))
      (node (ref "X2") (pin "CD2") (pinfunction "SHIELD_CD2") (pintype "bidirectional"))
      (node (ref "X2") (pin "GND1") (pinfunction "SHIELD_GND1") (pintype "bidirectional"))
      (node (ref "X2") (pin "GND3") (pinfunction "SHIELD_GND3") (pintype "bidirectional"))
      (node (ref "X3") (pin "1") (pinfunction "12_1") (pintype "passive"))
      (node (ref "X3") (pin "11") (pinfunction "2_11") (pintype "passive"))
      (node (ref "X4") (pin "3") (pinfunction "1_3") (pintype "passive"))
    )
    (net (code "17") (name "I2C_INT") (class "Default")
      (node (ref "IC3") (pin "10") (pinfunction "IO25_10") (pintype "bidirectional"))
      (node (ref "R1") (pin "1") (pinfunction "1_1") (pintype "passive"))
      (node (ref "U1") (pin "1") (pinfunction "~{IRQ}_1") (pintype "input"))
    )
    (net (code "18") (name "I2C_SCL") (class "Default")
      (node (ref "IC3") (pin "12") (pinfunction "IO27_12") (pintype "bidirectional"))
      (node (ref "R24") (pin "2") (pinfunction "2_2") (pintype "passive"))
      (node (ref "TP100") (pin "P$1") (pinfunction "1_P$1") (pintype "bidirectional"))
      (node (ref "TP114") (pin "P$1") (pinfunction "1_P$1") (pintype "bidirectional"))
      (node (ref "TP3") (pin "P$1") (pinfunction "1_P$1") (pintype "bidirectional"))
      (node (ref "U1") (pin "2") (pinfunction "SCL_2") (pintype "input"))
      (node (ref "X3") (pin "6") (pinfunction "7_6") (pintype "passive"))
    )
    (net (code "19") (name "I2C_SDA") (class "Default")
      (node (ref "IC3") (pin "11") (pinfunction "IO26_11") (pintype "bidirectional"))
      (node (ref "R23") (pin "2") (pinfunction "2_2") (pintype "passive"))
      (node (ref "TP101") (pin "P$1") (pinfunction "1_P$1") (pintype "bidirectional"))
      (node (ref "TP115") (pin "P$1") (pinfunction "1_P$1") (pintype "bidirectional"))
      (node (ref "TP2") (pin "P$1") (pinfunction "1_P$1") (pintype "bidirectional"))
      (node (ref "U1") (pin "3") (pinfunction "SDA_3") (pintype "input"))
      (node (ref "X3") (pin "7") (pinfunction "6_7") (pintype "passive"))
    )
    (net (code "20") (name "L-MISO") (class "Default")
      (node (ref "J2") (pin "1") (pinfunction "1_1") (pintype "passive"))
      (node (ref "U2") (pin "16") (pinfunction "PB4_16") (pintype "bidirectional"))
    )
    (net (code "21") (name "L-MOSI") (class "Default")
      (node (ref "J2") (pin "4") (pinfunction "4_4") (pintype "passive"))
      (node (ref "U2") (pin "15") (pinfunction "PB3_15") (pintype "bidirectional"))
    )
    (net (code "22") (name "L-RST") (class "Default")
      (node (ref "J2") (pin "5") (pinfunction "5_5") (pintype "passive"))
      (node (ref "U2") (pin "29") (pinfunction "PC6_29") (pintype "bidirectional"))
    )
    (net (code "23") (name "L-SCK") (class "Default")
      (node (ref "J2") (pin "3") (pinfunction "3_3") (pintype "passive"))
      (node (ref "U2") (pin "17") (pinfunction "PB5_17") (pintype "bidirectional"))
    )
    (net (code "24") (name "LCD_BUSY") (class "Default")
      (node (ref "IC3") (pin "36") (pinfunction "IO22_36") (pintype "bidirectional"))
      (node (ref "TP118") (pin "P$1") (pinfunction "1_P$1") (pintype "bidirectional"))
      (node (ref "X1") (pin "16") (pinfunction "16_16") (pintype "passive"))
    )
    (net (code "25") (name "LCD_CS") (class "Default")
      (node (ref "IC3") (pin "31") (pinfunction "IO19_31") (pintype "bidirectional"))
      (node (ref "TP109") (pin "P$1") (pinfunction "1_P$1") (pintype "bidirectional"))
      (node (ref "X1") (pin "13") (pinfunction "13_13") (pintype "passive"))
    )
    (net (code "26") (name "LCD_D{slash}~{S}") (class "Default")
      (node (ref "IC3") (pin "33") (pinfunction "IO21_33") (pintype "bidirectional"))
      (node (ref "TP111") (pin "P$1") (pinfunction "1_P$1") (pintype "bidirectional"))
      (node (ref "X1") (pin "14") (pinfunction "14_14") (pintype "passive"))
    )
    (net (code "27") (name "LCD_MOSI") (class "Default")
      (node (ref "IC3") (pin "29") (pinfunction "IO5_29") (pintype "bidirectional"))
      (node (ref "TP107") (pin "P$1") (pinfunction "1_P$1") (pintype "bidirectional"))
      (node (ref "X1") (pin "11") (pinfunction "11_11") (pintype "passive"))
    )
    (net (code "28") (name "LCD_SCK") (class "Default")
      (node (ref "IC3") (pin "30") (pinfunction "IO18_30") (pintype "bidirectional"))
      (node (ref "TP108") (pin "P$1") (pinfunction "1_P$1") (pintype "bidirectional"))
      (node (ref "X1") (pin "12") (pinfunction "12_12") (pintype "passive"))
    )
    (net (code "29") (name "LCD_VDD") (class "Default")
      (node (ref "C42") (pin "1") (pinfunction "1_1") (pintype "passive"))
      (node (ref "R26") (pin "2") (pinfunction "2_2") (pintype "passive"))
      (node (ref "X1") (pin "7") (pinfunction "7_7") (pintype "passive"))
    )
    (net (code "30") (name "LCD_~{RESET}") (class "Default")
      (node (ref "IC3") (pin "37") (pinfunction "IO23_37") (pintype "bidirectional"))
      (node (ref "TP113") (pin "P$1") (pinfunction "1_P$1") (pintype "bidirectional"))
      (node (ref "X1") (pin "15") (pinfunction "15_15") (pintype "passive"))
    )
    (net (code "31") (name "N$49") (class "Default")
      (node (ref "F2") (pin "1") (pinfunction "1_1") (pintype "bidirectional"))
      (node (ref "IC4") (pin "5") (pinfunction "BAT_5") (pintype "bidirectional"))
      (node (ref "S3") (pin "1") (pinfunction "1_1") (pintype "passive"))
      (node (ref "S3") (pin "4") (pinfunction "4_4") (pintype "passive"))
    )
    (net (code "32") (name "Net-(C25-Pad1)") (class "Default")
      (node (ref "C25") (pin "1") (pinfunction "1_1") (pintype "passive"))
      (node (ref "D7") (pin "A") (pinfunction "A_A") (pintype "passive"))
      (node (ref "D8") (pin "C") (pinfunction "C_C") (pintype "passive"))
    )
    (net (code "33") (name "Net-(D4-PadA)") (class "Default")
      (node (ref "D4") (pin "A") (pinfunction "A_A") (pintype "passive"))
      (node (ref "R3") (pin "1") (pinfunction "1_1") (pintype "passive"))
    )
    (net (code "34") (name "Net-(D5-PadA)") (class "Default")
      (node (ref "D5") (pin "A") (pinfunction "A_A") (pintype "passive"))
      (node (ref "R14") (pin "1") (pinfunction "1_1") (pintype "passive"))
    )
    (net (code "35") (name "Net-(D6-PadA)") (class "Default")
      (node (ref "D6") (pin "A") (pinfunction "A_A") (pintype "passive"))
      (node (ref "R12") (pin "1") (pinfunction "1_1") (pintype "passive"))
    )
    (net (code "36") (name "Net-(DB1-A)") (class "Default")
      (node (ref "DB1") (pin "2") (pinfunction "A_2") (pintype "passive"))
      (node (ref "R39") (pin "2") (pinfunction "2_2") (pintype "passive"))
    )
    (net (code "37") (name "Net-(DB2-A)") (class "Default")
      (node (ref "DB2") (pin "2") (pinfunction "A_2") (pintype "passive"))
      (node (ref "R40") (pin "2") (pinfunction "2_2") (pintype "passive"))
    )
    (net (code "38") (name "Net-(DB3-A)") (class "Default")
      (node (ref "DB3") (pin "2") (pinfunction "A_2") (pintype "passive"))
      (node (ref "R41") (pin "2") (pinfunction "2_2") (pintype "passive"))
    )
    (net (code "39") (name "Net-(DD1-Pad1)") (class "Default")
      (node (ref "DD1") (pin "1") (pinfunction "1_1") (pintype "passive"))
      (node (ref "R42") (pin "2") (pinfunction "2_2") (pintype "passive"))
    )
    (net (code "40") (name "Net-(DD1-Pad3)") (class "Default")
      (node (ref "DD1") (pin "3") (pinfunction "3_3") (pintype "passive"))
      (node (ref "R43") (pin "2") (pinfunction "2_2") (pintype "passive"))
    )
    (net (code "41") (name "Net-(DY1-A)") (class "Default")
      (node (ref "DY1") (pin "2") (pinfunction "A_2") (pintype "passive"))
      (node (ref "R2") (pin "2") (pinfunction "2_2") (pintype "passive"))
    )
    (net (code "42") (name "Net-(DY2-A)") (class "Default")
      (node (ref "DY2") (pin "2") (pinfunction "A_2") (pintype "passive"))
      (node (ref "R9") (pin "2") (pinfunction "2_2") (pintype "passive"))
    )
    (net (code "43") (name "Net-(DY3-A)") (class "Default")
      (node (ref "DY3") (pin "2") (pinfunction "A_2") (pintype "passive"))
      (node (ref "R10") (pin "2") (pinfunction "2_2") (pintype "passive"))
    )
    (net (code "44") (name "Net-(DY4-A)") (class "Default")
      (node (ref "DY4") (pin "2") (pinfunction "A_2") (pintype "passive"))
      (node (ref "R11") (pin "2") (pinfunction "2_2") (pintype "passive"))
    )
    (net (code "45") (name "Net-(DY5-A)") (class "Default")
      (node (ref "DY5") (pin "2") (pinfunction "A_2") (pintype "passive"))
      (node (ref "R27") (pin "2") (pinfunction "2_2") (pintype "passive"))
    )
    (net (code "46") (name "Net-(DY6-A)") (class "Default")
      (node (ref "DY6") (pin "2") (pinfunction "A_2") (pintype "passive"))
      (node (ref "R33") (pin "2") (pinfunction "2_2") (pintype "passive"))
    )
    (net (code "47") (name "Net-(DY7-A)") (class "Default")
      (node (ref "DY7") (pin "2") (pinfunction "A_2") (pintype "passive"))
      (node (ref "R34") (pin "2") (pinfunction "2_2") (pintype "passive"))
    )
    (net (code "48") (name "Net-(DY8-A)") (class "Default")
      (node (ref "DY8") (pin "2") (pinfunction "A_2") (pintype "passive"))
      (node (ref "R38") (pin "2") (pinfunction "2_2") (pintype "passive"))
    )
    (net (code "49") (name "Net-(IC1-DTR)") (class "Default")
      (node (ref "IC1") (pin "28") (pinfunction "DTR_28") (pintype "output"))
      (node (ref "Q4") (pin "2") (pinfunction "E_2") (pintype "passive"))
      (node (ref "R18") (pin "1") (pinfunction "1_1") (pintype "passive"))
    )
    (net (code "50") (name "Net-(IC1-RTS)") (class "Default")
      (node (ref "IC1") (pin "24") (pinfunction "RTS_24") (pintype "output"))
      (node (ref "Q3") (pin "2") (pinfunction "E_2") (pintype "passive"))
      (node (ref "R15") (pin "1") (pinfunction "1_1") (pintype "passive"))
    )
    (net (code "51") (name "Net-(IC1-~{RST})") (class "Default")
      (node (ref "IC1") (pin "9") (pinfunction "~{RST}_9") (pintype "bidirectional"))
      (node (ref "R13") (pin "2") (pinfunction "2_2") (pintype "passive"))
    )
    (net (code "52") (name "Net-(IC3-CLK)") (class "Default")
      (node (ref "IC3") (pin "20") (pinfunction "CLK_20") (pintype "bidirectional"))
      (node (ref "TP130") (pin "P$1") (pinfunction "1_P$1") (pintype "bidirectional"))
    )
    (net (code "53") (name "Net-(IC3-CND)") (class "Default")
      (node (ref "IC3") (pin "19") (pinfunction "CND_19") (pintype "bidirectional"))
      (node (ref "TP128") (pin "P$1") (pinfunction "1_P$1") (pintype "bidirectional"))
    )
    (net (code "54") (name "Net-(IC3-SD0)") (class "Default")
      (node (ref "IC3") (pin "21") (pinfunction "SD0_21") (pintype "bidirectional"))
      (node (ref "TP131") (pin "P$1") (pinfunction "1_P$1") (pintype "bidirectional"))
    )
    (net (code "55") (name "Net-(IC3-SD1)") (class "Default")
      (node (ref "IC3") (pin "22") (pinfunction "SD1_22") (pintype "bidirectional"))
      (node (ref "TP132") (pin "P$1") (pinfunction "1_P$1") (pintype "bidirectional"))
    )
    (net (code "56") (name "Net-(IC3-SD2)") (class "Default")
      (node (ref "IC3") (pin "17") (pinfunction "SD2_17") (pintype "bidirectional"))
      (node (ref "TP126") (pin "P$1") (pinfunction "1_P$1") (pintype "bidirectional"))
    )
    (net (code "57") (name "Net-(IC3-SD3)") (class "Default")
      (node (ref "IC3") (pin "18") (pinfunction "SD3_18") (pintype "bidirectional"))
      (node (ref "TP127") (pin "P$1") (pinfunction "1_P$1") (pintype "bidirectional"))
    )
    (net (code "58") (name "Net-(IC3-SENSOR_VN)") (class "Default")
      (node (ref "C29") (pin "2") (pinfunction "2_2") (pintype "passive"))
      (node (ref "IC3") (pin "5") (pinfunction "SENSOR_VN_5") (pintype "bidirectional"))
    )
    (net (code "59") (name "Net-(IC3-SENSOR_VP)") (class "Default")
      (node (ref "C28") (pin "2") (pinfunction "2_2") (pintype "passive"))
      (node (ref "IC3") (pin "4") (pinfunction "SENSOR_VP_4") (pintype "bidirectional"))
    )
    (net (code "60") (name "Net-(IC4-CE)") (class "Default")
      (node (ref "C23") (pin "2") (pinfunction "2_2") (pintype "passive"))
      (node (ref "C24") (pin "1") (pinfunction "1_1") (pintype "passive"))
      (node (ref "IC4") (pin "4") (pinfunction "VCC_4") (pintype "bidirectional"))
      (node (ref "IC4") (pin "8") (pinfunction "CE_8") (pintype "bidirectional"))
      (node (ref "R30") (pin "2") (pinfunction "2_2") (pintype "passive"))
      (node (ref "R32") (pin "2") (pinfunction "2_2") (pintype "passive"))
    )
    (net (code "61") (name "Net-(IC4-PROG)") (class "Default")
      (node (ref "IC4") (pin "2") (pinfunction "PROG_2") (pintype "bidirectional"))
      (node (ref "R29") (pin "1") (pinfunction "1_1") (pintype "passive"))
    )
    (net (code "62") (name "Net-(Q3-B)") (class "Default")
      (node (ref "Q3") (pin "1") (pinfunction "B_1") (pintype "passive"))
      (node (ref "R18") (pin "2") (pinfunction "2_2") (pintype "passive"))
    )
    (net (code "63") (name "Net-(Q4-B)") (class "Default")
      (node (ref "Q4") (pin "1") (pinfunction "B_1") (pintype "passive"))
      (node (ref "R15") (pin "2") (pinfunction "2_2") (pintype "passive"))
    )
    (net (code "64") (name "Net-(Q5-D)") (class "Default")
      (node (ref "C25") (pin "2") (pinfunction "2_2") (pintype "passive"))
      (node (ref "D9") (pin "A") (pinfunction "A_A") (pintype "passive"))
      (node (ref "L1") (pin "2") (pinfunction "2_2") (pintype "passive"))
      (node (ref "Q5") (pin "3") (pinfunction "D_3") (pintype "passive"))
    )
    (net (code "65") (name "Net-(Q6-C)") (class "Default")
      (node (ref "Q6") (pin "3") (pinfunction "C_3") (pintype "passive"))
      (node (ref "R28") (pin "1") (pinfunction "1_1") (pintype "passive"))
      (node (ref "T3") (pin "1") (pinfunction "G_1") (pintype "passive"))
    )
    (net (code "66") (name "Net-(R29-Pad2)") (class "Default")
      (node (ref "R29") (pin "2") (pinfunction "2_2") (pintype "passive"))
      (node (ref "R35") (pin "1") (pinfunction "1_1") (pintype "passive"))
      (node (ref "SJ3") (pin "2") (pinfunction "2_2") (pintype "passive"))
    )
    (net (code "67") (name "Net-(TP139-1)") (class "Default")
      (node (ref "F1") (pin "1") (pinfunction "1_1") (pintype "bidirectional"))
      (node (ref "TP139") (pin "P$1") (pinfunction "1_P$1") (pintype "bidirectional"))
      (node (ref "USB1") (pin "1") (pinfunction "1_1") (pintype "input"))
    )
    (net (code "68") (name "Net-(U1-REXT)") (class "Default")
      (node (ref "R37") (pin "2") (pinfunction "2_2") (pintype "passive"))
      (node (ref "U1") (pin "7") (pinfunction "REXT_7") (pintype "input"))
    )
    (net (code "69") (name "Net-(U1-V_REG)") (class "Default")
      (node (ref "C45") (pin "1") (pinfunction "1_1") (pintype "passive"))
      (node (ref "U1") (pin "5") (pinfunction "V_REG_5") (pintype "input"))
    )
    (net (code "70") (name "Net-(U2-AREF)") (class "Default")
      (node (ref "C1") (pin "1") (pinfunction "1_1") (pintype "passive"))
      (node (ref "U2") (pin "20") (pinfunction "AREF_20") (pintype "input"))
    )
    (net (code "71") (name "PREVGH") (class "Default")
      (node (ref "C32") (pin "2") (pinfunction "2_2") (pintype "passive"))
      (node (ref "D9") (pin "C") (pinfunction "C_C") (pintype "passive"))
      (node (ref "TP104") (pin "P$1") (pinfunction "1_P$1") (pintype "bidirectional"))
      (node (ref "X1") (pin "4") (pinfunction "4_4") (pintype "passive"))
    )
    (net (code "72") (name "PREVGL") (class "Default")
      (node (ref "C36") (pin "2") (pinfunction "2_2") (pintype "passive"))
      (node (ref "D8") (pin "A") (pinfunction "A_A") (pintype "passive"))
      (node (ref "TP105") (pin "P$1") (pinfunction "1_P$1") (pintype "bidirectional"))
      (node (ref "X1") (pin "2") (pinfunction "2_2") (pintype "passive"))
    )
    (net (code "73") (name "RESE") (class "Default")
      (node (ref "Q5") (pin "2") (pinfunction "S_2") (pintype "passive"))
      (node (ref "R19") (pin "1") (pinfunction "1_1") (pintype "passive"))
      (node (ref "TP123") (pin "P$1") (pinfunction "1_P$1") (pintype "bidirectional"))
      (node (ref "X1") (pin "22") (pinfunction "22_22") (pintype "passive"))
    )
    (net (code "74") (name "RLS-1") (class "Default")
      (node (ref "R42") (pin "1") (pinfunction "1_1") (pintype "passive"))
      (node (ref "U2") (pin "23") (pinfunction "PC0_23") (pintype "bidirectional"))
    )
    (net (code "75") (name "RLS-2") (class "Default")
      (node (ref "R43") (pin "1") (pinfunction "1_1") (pintype "passive"))
      (node (ref "U2") (pin "24") (pinfunction "PC1_24") (pintype "bidirectional"))
    )
    (net (code "76") (name "SD_CD") (class "Default")
      (node (ref "R31") (pin "2") (pinfunction "2_2") (pintype "passive"))
      (node (ref "U1") (pin "19") (pinfunction "ELE11_19") (pintype "output"))
      (node (ref "X2") (pin "CD1") (pinfunction "SHIELD_CD1") (pintype "bidirectional"))
    )
    (net (code "77") (name "SD_CLK") (class "Default")
      (node (ref "IC3") (pin "13") (pinfunction "IO14_13") (pintype "bidirectional"))
      (node (ref "R25") (pin "1") (pinfunction "1_1") (pintype "passive"))
      (node (ref "X2") (pin "5") (pinfunction "SCK_5") (pintype "bidirectional"))
    )
    (net (code "78") (name "SD_CMD") (class "Default")
      (node (ref "IC3") (pin "23") (pinfunction "IO15_23") (pintype "bidirectional"))
      (node (ref "R8") (pin "1") (pinfunction "1_1") (pintype "passive"))
      (node (ref "X2") (pin "3") (pinfunction "DI_3") (pintype "bidirectional"))
    )
    (net (code "79") (name "SD_DATA0") (class "Default")
      (node (ref "D2") (pin "A") (pinfunction "A_A") (pintype "passive"))
      (node (ref "IC3") (pin "24") (pinfunction "IO2_24") (pintype "bidirectional"))
      (node (ref "R5") (pin "1") (pinfunction "1_1") (pintype "passive"))
      (node (ref "X2") (pin "7") (pinfunction "DO_7") (pintype "bidirectional"))
    )
    (net (code "80") (name "SD_DATA3") (class "Default")
      (node (ref "IC3") (pin "16") (pinfunction "IO13_16") (pintype "bidirectional"))
      (node (ref "R17") (pin "1") (pinfunction "1_1") (pintype "passive"))
      (node (ref "X2") (pin "2") (pinfunction "CS_2") (pintype "bidirectional"))
    )
    (net (code "81") (name "SHT-GP1") (class "Default")
      (node (ref "J1") (pin "2") (pinfunction "2_2") (pintype "bidirectional"))
      (node (ref "U2") (pin "25") (pinfunction "PC2_25") (pintype "bidirectional"))
    )
    (net (code "82") (name "SHT-GP2") (class "Default")
      (node (ref "J1") (pin "1") (pinfunction "1_1") (pintype "bidirectional"))
      (node (ref "U2") (pin "26") (pinfunction "PC3_26") (pintype "bidirectional"))
    )
    (net (code "83") (name "SWBDG") (class "Default")
      (node (ref "C34") (pin "1") (pinfunction "1_1") (pintype "passive"))
      (node (ref "S3") (pin "2") (pinfunction "2_2") (pintype "passive"))
      (node (ref "S3") (pin "5") (pinfunction "5_5") (pintype "passive"))
      (node (ref "S4") (pin "2") (pinfunction "2_2") (pintype "passive"))
      (node (ref "S4") (pin "5") (pinfunction "5_5") (pintype "passive"))
      (node (ref "X4") (pin "1") (pinfunction "1_1") (pintype "passive"))
    )
    (net (code "84") (name "TEMP") (class "Default")
      (node (ref "IC4") (pin "1") (pinfunction "TEMP_1") (pintype "bidirectional"))
      (node (ref "R32") (pin "1") (pinfunction "1_1") (pintype "passive"))
      (node (ref "X4") (pin "2") (pinfunction "1_2") (pintype "passive"))
    )
    (net (code "85") (name "TLB-1") (class "Default")
      (node (ref "R39") (pin "1") (pinfunction "1_1") (pintype "passive"))
      (node (ref "U2") (pin "14") (pinfunction "PB2_14") (pintype "bidirectional"))
    )
    (net (code "86") (name "TLB-2") (class "Default")
      (node (ref "R40") (pin "1") (pinfunction "1_1") (pintype "passive"))
      (node (ref "U2") (pin "9") (pinfunction "PD5_9") (pintype "bidirectional"))
    )
    (net (code "87") (name "TLB-3") (class "Default")
      (node (ref "R41") (pin "1") (pinfunction "1_1") (pintype "passive"))
      (node (ref "U2") (pin "10") (pinfunction "PD6_10") (pintype "bidirectional"))
    )
    (net (code "88") (name "TSCL") (class "Default")
      (node (ref "X1") (pin "19") (pinfunction "19_19") (pintype "passive"))
    )
    (net (code "89") (name "TSDA") (class "Default")
      (node (ref "X1") (pin "18") (pinfunction "18_18") (pintype "passive"))
    )
    (net (code "90") (name "USB_DN_CON") (class "Default")
      (node (ref "IC1") (pin "5") (pinfunction "D-_5") (pintype "bidirectional"))
      (node (ref "TP137") (pin "P$1") (pinfunction "1_P$1") (pintype "bidirectional"))
      (node (ref "USB1") (pin "2") (pinfunction "2_2") (pintype "input"))
    )
    (net (code "91") (name "USB_DP_CON") (class "Default")
      (node (ref "IC1") (pin "4") (pinfunction "D+_4") (pintype "bidirectional"))
      (node (ref "TP138") (pin "P$1") (pinfunction "1_P$1") (pintype "bidirectional"))
      (node (ref "USB1") (pin "3") (pinfunction "3_3") (pintype "input"))
    )
    (net (code "92") (name "VBAT") (class "Default")
      (node (ref "F2") (pin "2") (pinfunction "2_2") (pintype "bidirectional"))
      (node (ref "R21") (pin "2") (pinfunction "2_2") (pintype "passive"))
      (node (ref "T1") (pin "3") (pinfunction "D_3") (pintype "passive"))
      (node (ref "TP110") (pin "P$1") (pinfunction "1_P$1") (pintype "bidirectional"))
    )
    (net (code "93") (name "VBAT_SENSE") (class "Default")
      (node (ref "C16") (pin "1") (pinfunction "1_1") (pintype "passive"))
      (node (ref "IC3") (pin "7") (pinfunction "IO35_7") (pintype "bidirectional"))
      (node (ref "R20") (pin "2") (pinfunction "2_2") (pintype "passive"))
      (node (ref "R21") (pin "1") (pinfunction "1_1") (pintype "passive"))
    )
    (net (code "94") (name "VCC") (class "Default")
      (node (ref "C14") (pin "1") (pinfunction "1_1") (pintype "passive"))
      (node (ref "C15") (pin "1") (pinfunction "1_1") (pintype "passive"))
      (node (ref "C18") (pin "1") (pinfunction "1_1") (pintype "passive"))
      (node (ref "D3") (pin "C") (pinfunction "C_C") (pintype "passive"))
      (node (ref "IC2") (pin "3") (pinfunction "IN_3") (pintype "input"))
      (node (ref "T1") (pin "2") (pinfunction "S_2") (pintype "passive"))
      (node (ref "TP129") (pin "P$1") (pinfunction "1_P$1") (pintype "bidirectional"))
    )
    (net (code "95") (name "VCOM") (class "Default")
      (node (ref "C38") (pin "2") (pinfunction "2_2") (pintype "passive"))
      (node (ref "X1") (pin "1") (pinfunction "1_1") (pintype "passive"))
    )
    (net (code "96") (name "VDD") (class "Default")
      (node (ref "C8") (pin "1") (pinfunction "1_1") (pintype "passive"))
      (node (ref "IC1") (pin "6") (pinfunction "VDD_6") (pintype "power_in"))
      (node (ref "R12") (pin "2") (pinfunction "2_2") (pintype "passive"))
      (node (ref "R13") (pin "1") (pinfunction "1_1") (pintype "passive"))
      (node (ref "R14") (pin "2") (pinfunction "2_2") (pintype "passive"))
      (node (ref "R3") (pin "2") (pinfunction "2_2") (pintype "passive"))
    )
    (net (code "97") (name "VGH") (class "Default")
      (node (ref "C21") (pin "2") (pinfunction "2_2") (pintype "passive"))
      (node (ref "X1") (pin "20") (pinfunction "20_20") (pintype "passive"))
    )
    (net (code "98") (name "VGL") (class "Default")
      (node (ref "C19") (pin "2") (pinfunction "2_2") (pintype "passive"))
      (node (ref "X1") (pin "21") (pinfunction "21_21") (pintype "passive"))
    )
    (net (code "99") (name "VPP") (class "Default")
      (node (ref "X1") (pin "6") (pinfunction "6_6") (pintype "passive"))
    )
    (net (code "100") (name "VSH") (class "Default")
      (node (ref "C33") (pin "2") (pinfunction "2_2") (pintype "passive"))
      (node (ref "X1") (pin "5") (pinfunction "5_5") (pintype "passive"))
    )
    (net (code "101") (name "VSL") (class "Default")
      (node (ref "C35") (pin "2") (pinfunction "2_2") (pintype "passive"))
      (node (ref "X1") (pin "3") (pinfunction "3_3") (pintype "passive"))
    )
    (net (code "102") (name "VUSB_SENSE") (class "Default")
      (node (ref "C10") (pin "1") (pinfunction "1_1") (pintype "passive"))
      (node (ref "IC3") (pin "6") (pinfunction "IO34_6") (pintype "bidirectional"))
      (node (ref "R6") (pin "2") (pinfunction "2_2") (pintype "passive"))
      (node (ref "R7") (pin "1") (pinfunction "1_1") (pintype "passive"))
    )
    (net (code "103") (name "WS2812_POWER") (class "Default")
      (node (ref "TP117") (pin "P$1") (pinfunction "1_P$1") (pintype "bidirectional"))
    )
    (net (code "104") (name "YCR-1") (class "Default")
      (node (ref "R2") (pin "1") (pinfunction "1_1") (pintype "passive"))
      (node (ref "U2") (pin "12") (pinfunction "PB0_12") (pintype "bidirectional"))
    )
    (net (code "105") (name "YCR-2") (class "Default")
      (node (ref "R9") (pin "1") (pinfunction "1_1") (pintype "passive"))
      (node (ref "U2") (pin "13") (pinfunction "PB1_13") (pintype "bidirectional"))
    )
    (net (code "106") (name "YCR-3") (class "Default")
      (node (ref "R10") (pin "1") (pinfunction "1_1") (pintype "passive"))
      (node (ref "U2") (pin "31") (pinfunction "PD1_31") (pintype "bidirectional"))
    )
    (net (code "107") (name "YCR-4") (class "Default")
      (node (ref "R11") (pin "1") (pinfunction "1_1") (pintype "passive"))
      (node (ref "U2") (pin "32") (pinfunction "PD2_32") (pintype "bidirectional"))
    )
    (net (code "108") (name "YCR-5") (class "Default")
      (node (ref "R27") (pin "1") (pinfunction "1_1") (pintype "passive"))
      (node (ref "U2") (pin "1") (pinfunction "PD3_1") (pintype "bidirectional"))
    )
    (net (code "109") (name "YCR-6") (class "Default")
      (node (ref "R33") (pin "1") (pinfunction "1_1") (pintype "passive"))
      (node (ref "U2") (pin "2") (pinfunction "PD4_2") (pintype "bidirectional"))
    )
    (net (code "110") (name "YCR-7") (class "Default")
      (node (ref "R34") (pin "1") (pinfunction "1_1") (pintype "passive"))
      (node (ref "U2") (pin "7") (pinfunction "PB6_7") (pintype "bidirectional"))
    )
    (net (code "111") (name "YCR-8") (class "Default")
      (node (ref "R38") (pin "1") (pinfunction "1_1") (pintype "passive"))
      (node (ref "U2") (pin "8") (pinfunction "PB7_8") (pintype "bidirectional"))
    )
    (net (code "112") (name "unconnected-(IC1-CTS-Pad23)") (class "Default")
      (node (ref "IC1") (pin "23") (pinfunction "CTS_23") (pintype "input"))
    )
    (net (code "113") (name "unconnected-(IC1-DCD-Pad1)") (class "Default")
      (node (ref "IC1") (pin "1") (pinfunction "DCD_1") (pintype "input"))
    )
    (net (code "114") (name "unconnected-(IC1-DSR-Pad27)") (class "Default")
      (node (ref "IC1") (pin "27") (pinfunction "DSR_27") (pintype "input"))
    )
    (net (code "115") (name "unconnected-(IC1-RI-Pad2)") (class "Default")
      (node (ref "IC1") (pin "2") (pinfunction "RI_2") (pintype "input"))
    )
    (net (code "116") (name "unconnected-(IC1-SUSPEND-Pad12)") (class "Default")
      (node (ref "IC1") (pin "12") (pinfunction "SUSPEND_12") (pintype "output"))
    )
    (net (code "117") (name "unconnected-(IC1-~{SUSPEND}-Pad11)") (class "Default")
      (node (ref "IC1") (pin "11") (pinfunction "~{SUSPEND}_11") (pintype "output"))
    )
    (net (code "118") (name "unconnected-(IC3-IO20-Pad32)") (class "Default")
      (node (ref "IC3") (pin "32") (pinfunction "IO20_32") (pintype "bidirectional"))
    )
    (net (code "119") (name "unconnected-(IC3-IO32-Pad8)") (class "Default")
      (node (ref "IC3") (pin "8") (pinfunction "IO32_8") (pintype "bidirectional"))
    )
    (net (code "120") (name "unconnected-(IC4-STDBY-Pad6)") (class "Default")
      (node (ref "IC4") (pin "6") (pinfunction "STDBY_6") (pintype "bidirectional"))
    )
    (net (code "121") (name "unconnected-(J1-Pad3)") (class "Default")
      (node (ref "J1") (pin "3") (pinfunction "3_3") (pintype "bidirectional"))
    )
    (net (code "122") (name "unconnected-(J1-Pad4)") (class "Default")
      (node (ref "J1") (pin "4") (pinfunction "4_4") (pintype "bidirectional"))
    )
    (net (code "123") (name "unconnected-(J3-Pad1)") (class "Default")
      (node (ref "J3") (pin "1") (pinfunction "1_1") (pintype "bidirectional"))
    )
    (net (code "124") (name "unconnected-(J3-Pad2)") (class "Default")
      (node (ref "J3") (pin "2") (pinfunction "2_2") (pintype "bidirectional"))
    )
    (net (code "125") (name "unconnected-(J3-Pad3)") (class "Default")
      (node (ref "J3") (pin "3") (pinfunction "3_3") (pintype "bidirectional"))
    )
    (net (code "126") (name "unconnected-(J3-Pad4)") (class "Default")
      (node (ref "J3") (pin "4") (pinfunction "4_4") (pintype "bidirectional"))
    )
    (net (code "127") (name "unconnected-(Q6-B-Pad1)") (class "Default")
      (node (ref "Q6") (pin "1") (pinfunction "B_1") (pintype "passive"))
    )
    (net (code "128") (name "unconnected-(S3-Pad3)") (class "Default")
      (node (ref "S3") (pin "3") (pinfunction "3_3") (pintype "passive"))
    )
    (net (code "129") (name "unconnected-(S3-Pad6)") (class "Default")
      (node (ref "S3") (pin "6") (pinfunction "6_6") (pintype "passive"))
    )
    (net (code "130") (name "unconnected-(S4-Pad3)") (class "Default")
      (node (ref "S4") (pin "3") (pinfunction "3_3") (pintype "passive"))
    )
    (net (code "131") (name "unconnected-(S4-Pad6)") (class "Default")
      (node (ref "S4") (pin "6") (pinfunction "6_6") (pintype "passive"))
    )
    (net (code "132") (name "unconnected-(U1-ELE0-Pad8)") (class "Default")
      (node (ref "U1") (pin "8") (pinfunction "ELE0_8") (pintype "output"))
    )
    (net (code "133") (name "unconnected-(U1-ELE1-Pad9)") (class "Default")
      (node (ref "U1") (pin "9") (pinfunction "ELE1_9") (pintype "output"))
    )
    (net (code "134") (name "unconnected-(U1-ELE2-Pad10)") (class "Default")
      (node (ref "U1") (pin "10") (pinfunction "ELE2_10") (pintype "output"))
    )
    (net (code "135") (name "unconnected-(U1-ELE3-Pad11)") (class "Default")
      (node (ref "U1") (pin "11") (pinfunction "ELE3_11") (pintype "output"))
    )
    (net (code "136") (name "unconnected-(U1-ELE4-Pad12)") (class "Default")
      (node (ref "U1") (pin "12") (pinfunction "ELE4_12") (pintype "output"))
    )
    (net (code "137") (name "unconnected-(U1-ELE5-Pad13)") (class "Default")
      (node (ref "U1") (pin "13") (pinfunction "ELE5_13") (pintype "output"))
    )
    (net (code "138") (name "unconnected-(U1-ELE6-Pad14)") (class "Default")
      (node (ref "U1") (pin "14") (pinfunction "ELE6_14") (pintype "output"))
    )
    (net (code "139") (name "unconnected-(U1-ELE7-Pad15)") (class "Default")
      (node (ref "U1") (pin "15") (pinfunction "ELE7_15") (pintype "output"))
    )
    (net (code "140") (name "unconnected-(U1-ELE8-Pad16)") (class "Default")
      (node (ref "U1") (pin "16") (pinfunction "ELE8_16") (pintype "output"))
    )
    (net (code "141") (name "unconnected-(U1-ELE10-Pad18)") (class "Default")
      (node (ref "U1") (pin "18") (pinfunction "ELE10_18") (pintype "output"))
    )
    (net (code "142") (name "unconnected-(U2-ADC6-Pad19)") (class "Default")
      (node (ref "U2") (pin "19") (pinfunction "ADC6_19") (pintype "input"))
    )
    (net (code "143") (name "unconnected-(U2-ADC7-Pad22)") (class "Default")
      (node (ref "U2") (pin "22") (pinfunction "ADC7_22") (pintype "input"))
    )
    (net (code "144") (name "unconnected-(U2-PC4-Pad27)") (class "Default")
      (node (ref "U2") (pin "27") (pinfunction "PC4_27") (pintype "bidirectional"))
    )
    (net (code "145") (name "unconnected-(U2-PC5-Pad28)") (class "Default")
      (node (ref "U2") (pin "28") (pinfunction "PC5_28") (pintype "bidirectional"))
    )
    (net (code "146") (name "unconnected-(U2-PD0-Pad30)") (class "Default")
      (node (ref "U2") (pin "30") (pinfunction "PD0_30") (pintype "bidirectional"))
    )
    (net (code "147") (name "unconnected-(U2-PD7-Pad11)") (class "Default")
      (node (ref "U2") (pin "11") (pinfunction "PD7_11") (pintype "bidirectional"))
    )
    (net (code "148") (name "unconnected-(USB1-Pad4)") (class "Default")
      (node (ref "USB1") (pin "4") (pinfunction "4_4") (pintype "input"))
    )
    (net (code "149") (name "unconnected-(X1-Pad24)") (class "Default")
      (node (ref "X1") (pin "24") (pinfunction "24_24") (pintype "passive"))
    )
    (net (code "150") (name "unconnected-(X2-NC-Pad1)") (class "Default")
      (node (ref "X2") (pin "1") (pinfunction "NC_1") (pintype "bidirectional"))
    )
    (net (code "151") (name "unconnected-(X2-RSV-Pad8)") (class "Default")
      (node (ref "X2") (pin "8") (pinfunction "RSV_8") (pintype "bidirectional"))
    )
    (net (code "152") (name "unconnected-(X3-5-Pad8)") (class "Default")
      (node (ref "X3") (pin "8") (pinfunction "5_8") (pintype "passive"))
    )
    (net (code "153") (name "unconnected-(X3-11-Pad2)") (class "Default")
      (node (ref "X3") (pin "2") (pinfunction "11_2") (pintype "passive"))
    )
  )
)
